# bop_pcb.net
KiCad netlist of a schematic drawn in EAGLE
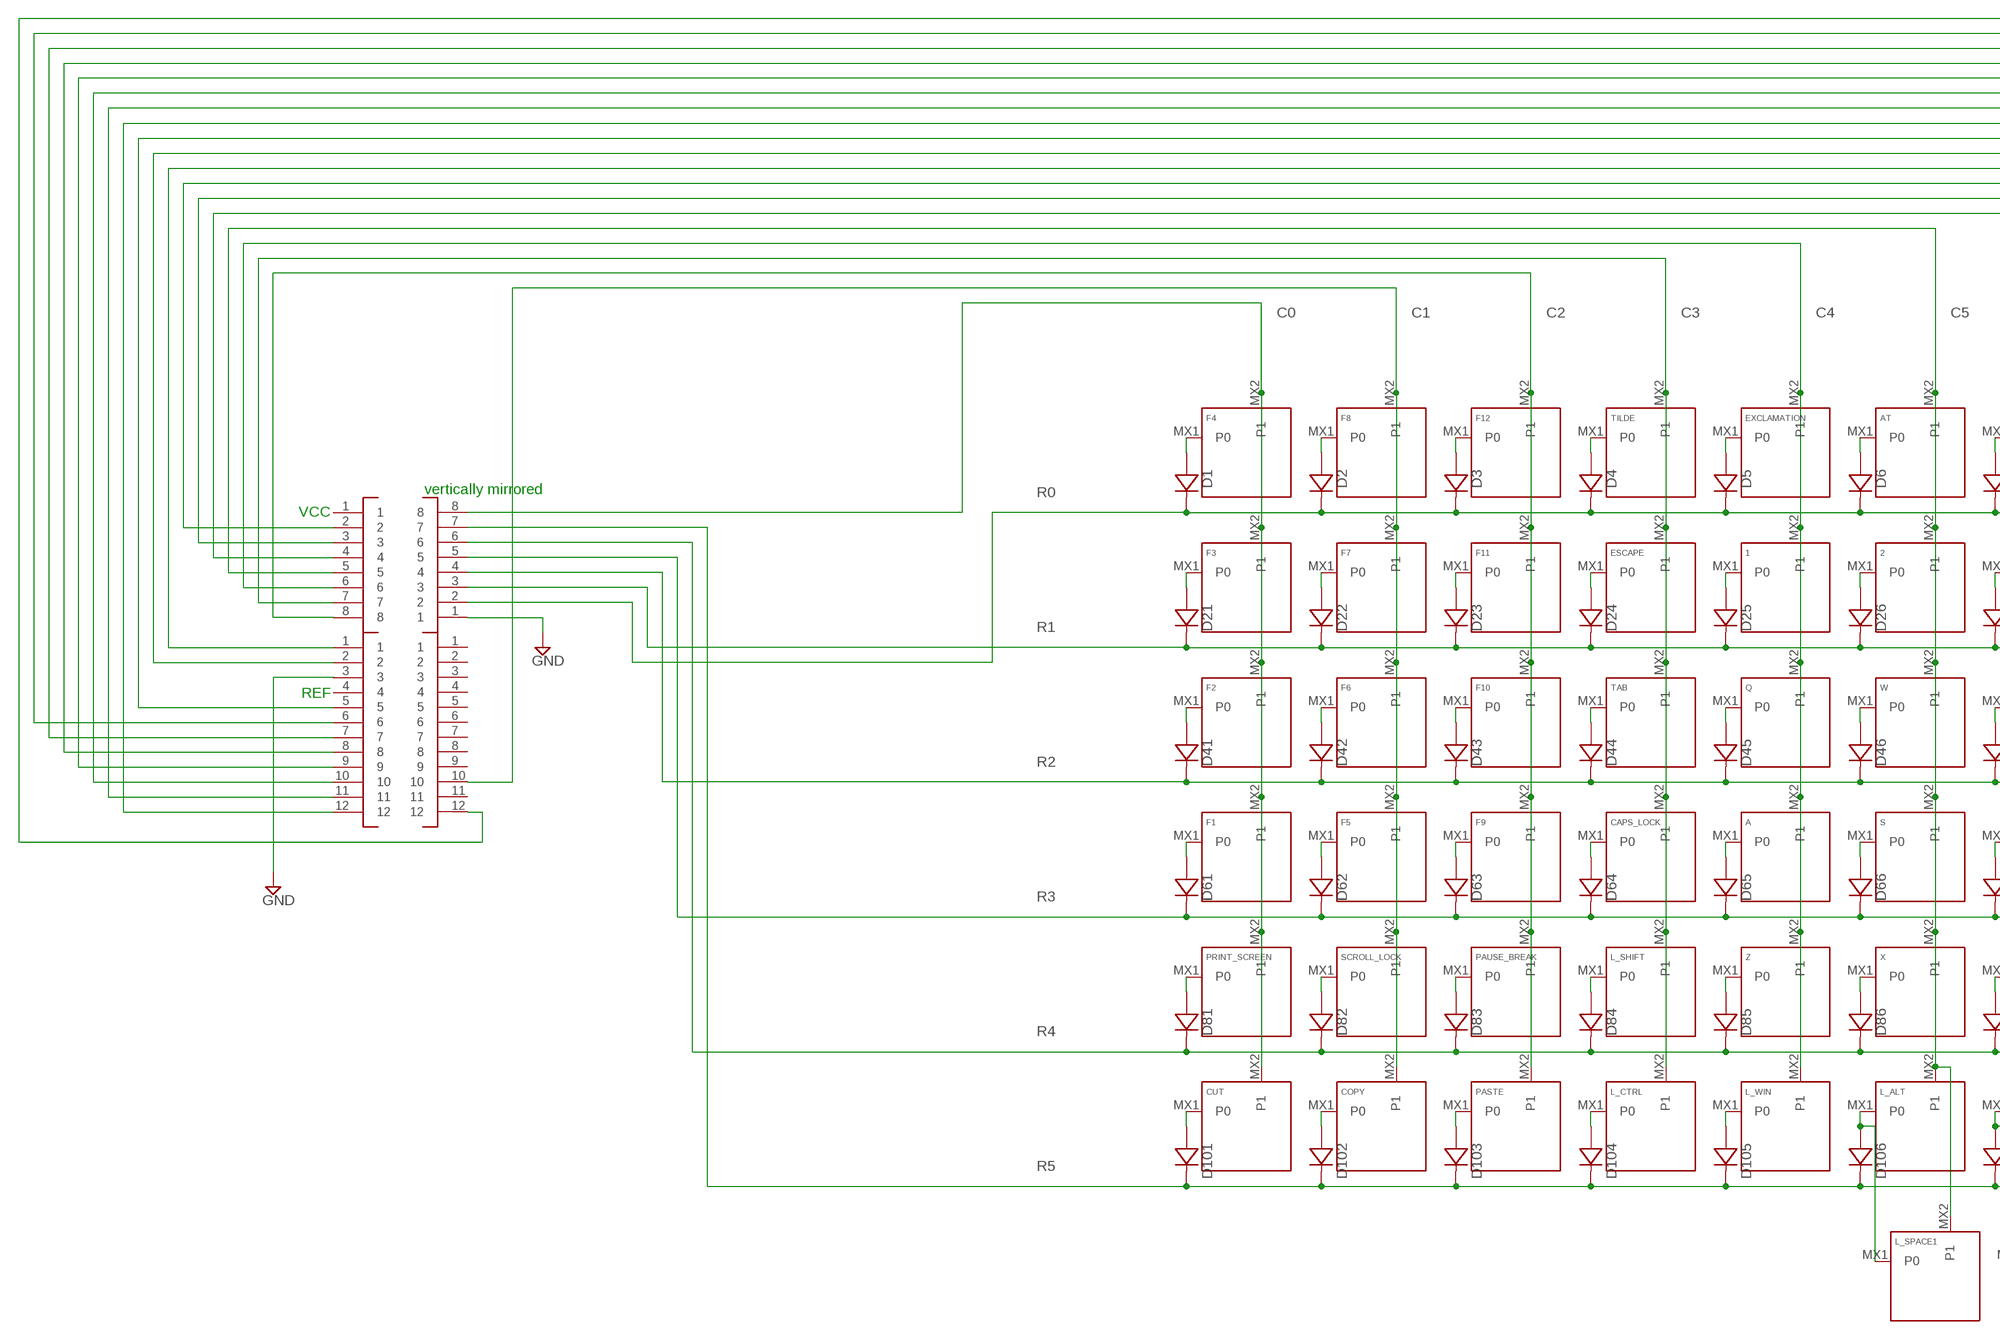
[diagram p0: schematic, sheet 1, part 1 of 2]
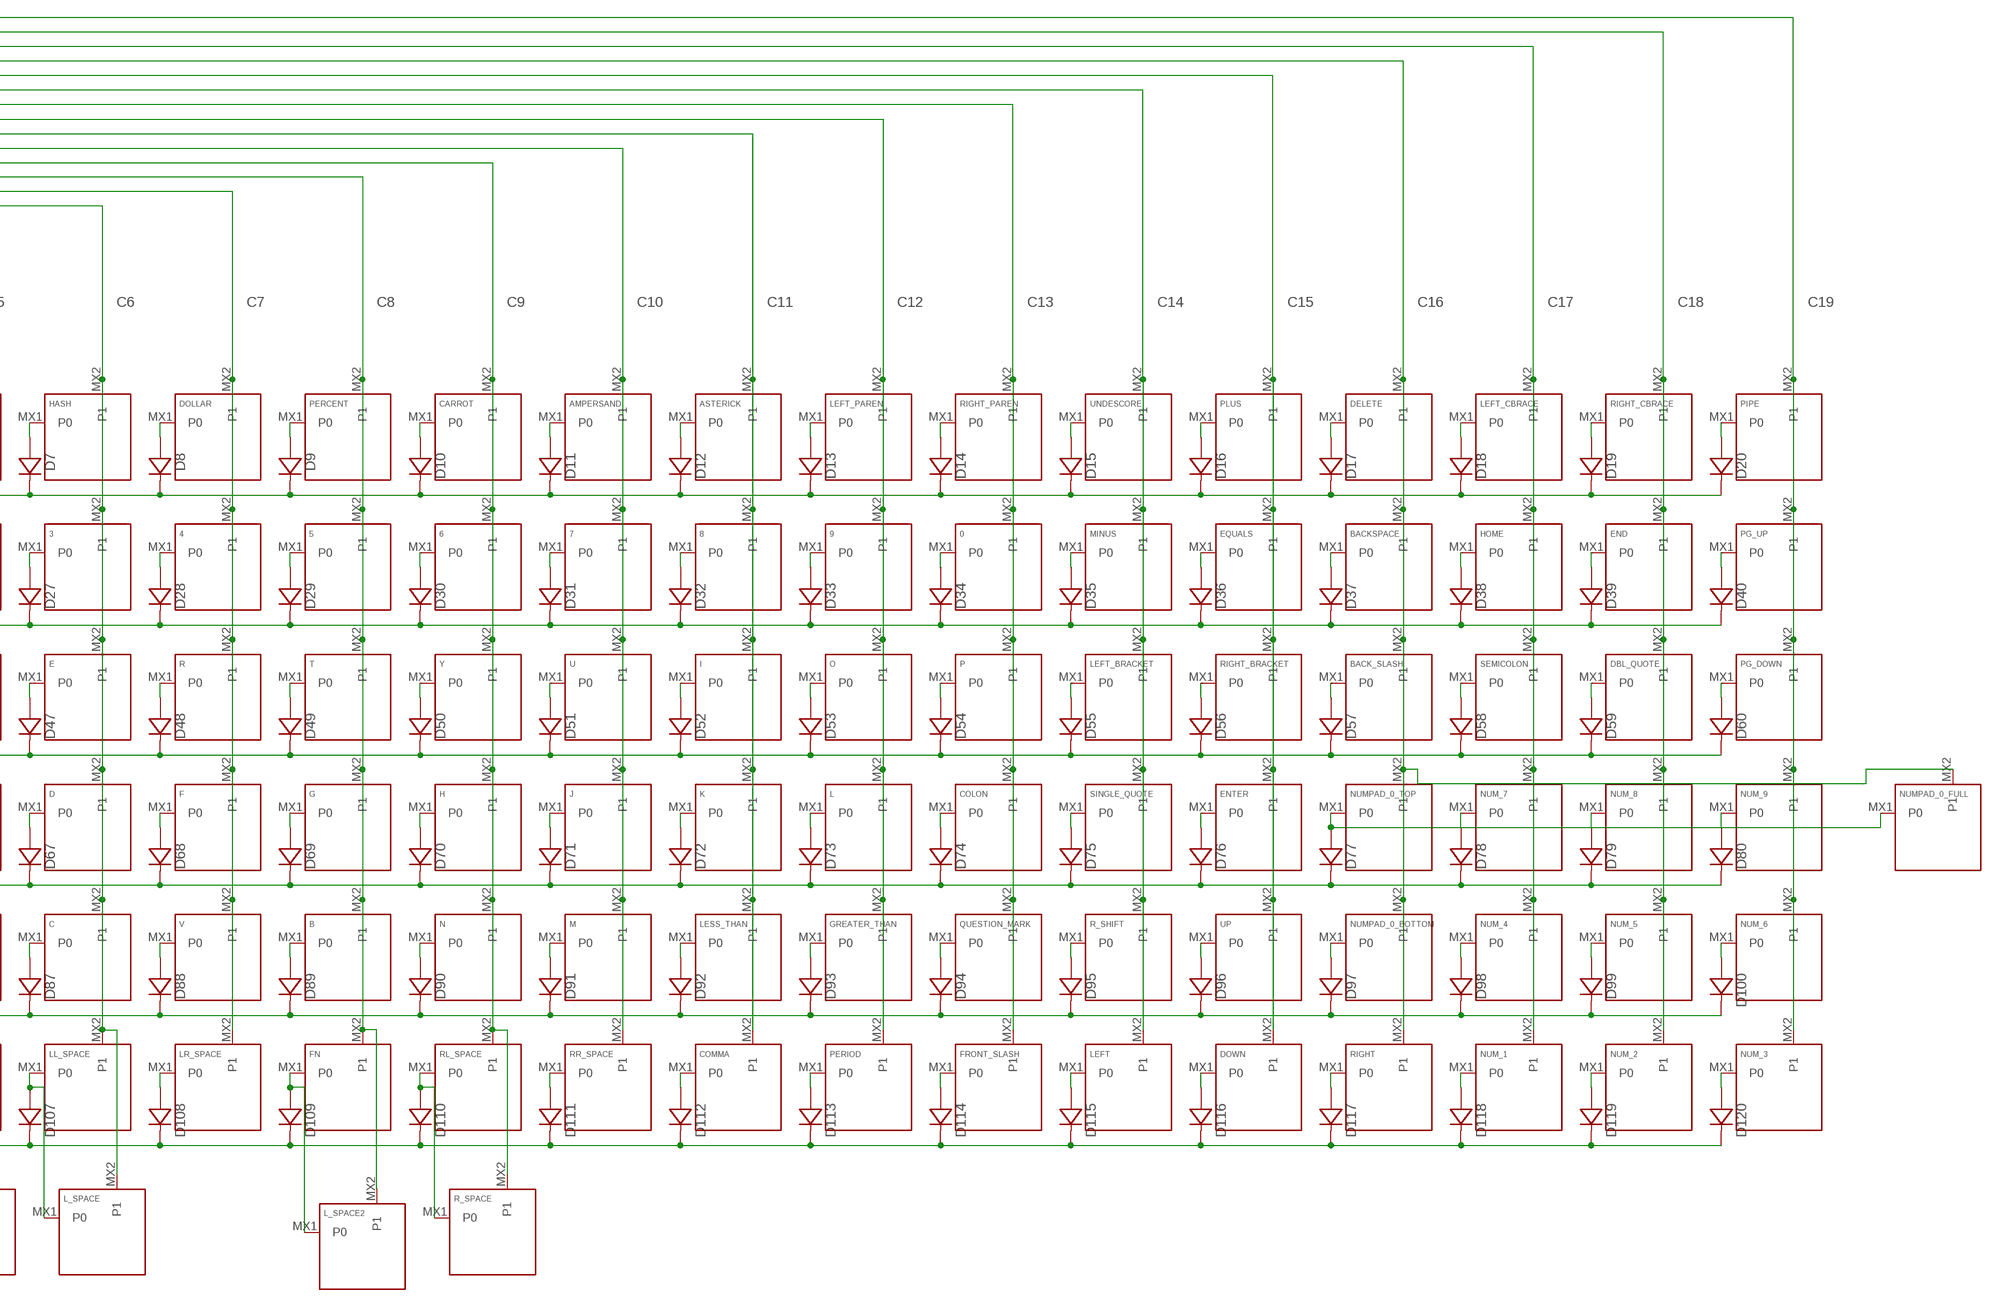
[diagram p1: schematic, sheet 1, part 2 of 2]

(export (version "E")
  (design (tool "Eeschema 10.0.6"))
  (components
    (comp (ref "0")
      (value "KEYSWITCH-PLAIN-MX-1U")
      (footprint "eagle-import:MX-1U")
      (libsource (lib "eagle-import") (part "KEYSWITCH-PLAIN-MX-1U"))
    )
    (comp (ref "1")
      (value "KEYSWITCH-PLAIN-MX-1U")
      (footprint "eagle-import:MX-1U")
      (libsource (lib "eagle-import") (part "KEYSWITCH-PLAIN-MX-1U"))
    )
    (comp (ref "2")
      (value "KEYSWITCH-PLAIN-MX-1U")
      (footprint "eagle-import:MX-1U")
      (libsource (lib "eagle-import") (part "KEYSWITCH-PLAIN-MX-1U"))
    )
    (comp (ref "3")
      (value "KEYSWITCH-PLAIN-MX-1U")
      (footprint "eagle-import:MX-1U")
      (libsource (lib "eagle-import") (part "KEYSWITCH-PLAIN-MX-1U"))
    )
    (comp (ref "4")
      (value "KEYSWITCH-PLAIN-MX-1U")
      (footprint "eagle-import:MX-1U")
      (libsource (lib "eagle-import") (part "KEYSWITCH-PLAIN-MX-1U"))
    )
    (comp (ref "5")
      (value "KEYSWITCH-PLAIN-MX-1U")
      (footprint "eagle-import:MX-1U")
      (libsource (lib "eagle-import") (part "KEYSWITCH-PLAIN-MX-1U"))
    )
    (comp (ref "6")
      (value "KEYSWITCH-PLAIN-MX-1U")
      (footprint "eagle-import:MX-1U")
      (libsource (lib "eagle-import") (part "KEYSWITCH-PLAIN-MX-1U"))
    )
    (comp (ref "7")
      (value "KEYSWITCH-PLAIN-MX-1U")
      (footprint "eagle-import:MX-1U")
      (libsource (lib "eagle-import") (part "KEYSWITCH-PLAIN-MX-1U"))
    )
    (comp (ref "8")
      (value "KEYSWITCH-PLAIN-MX-1U")
      (footprint "eagle-import:MX-1U")
      (libsource (lib "eagle-import") (part "KEYSWITCH-PLAIN-MX-1U"))
    )
    (comp (ref "9")
      (value "KEYSWITCH-PLAIN-MX-1U")
      (footprint "eagle-import:MX-1U")
      (libsource (lib "eagle-import") (part "KEYSWITCH-PLAIN-MX-1U"))
    )
    (comp (ref "A")
      (value "KEYSWITCH-PLAIN-MX-1U")
      (footprint "eagle-import:MX-1U")
      (libsource (lib "eagle-import") (part "KEYSWITCH-PLAIN-MX-1U"))
    )
    (comp (ref "AMPERSAND")
      (value "KEYSWITCH-PLAIN-MX-1U")
      (footprint "eagle-import:MX-1U")
      (libsource (lib "eagle-import") (part "KEYSWITCH-PLAIN-MX-1U"))
    )
    (comp (ref "ASTERICK")
      (value "KEYSWITCH-PLAIN-MX-1U")
      (footprint "eagle-import:MX-1U")
      (libsource (lib "eagle-import") (part "KEYSWITCH-PLAIN-MX-1U"))
    )
    (comp (ref "AT")
      (value "KEYSWITCH-PLAIN-MX-1U")
      (footprint "eagle-import:MX-1U")
      (libsource (lib "eagle-import") (part "KEYSWITCH-PLAIN-MX-1U"))
    )
    (comp (ref "B")
      (value "KEYSWITCH-PLAIN-MX-1U")
      (footprint "eagle-import:MX-1U")
      (libsource (lib "eagle-import") (part "KEYSWITCH-PLAIN-MX-1U"))
    )
    (comp (ref "BACKSPACE")
      (value "KEYSWITCH-PLAIN-MX-1U")
      (footprint "eagle-import:MX-1U")
      (libsource (lib "eagle-import") (part "KEYSWITCH-PLAIN-MX-1U"))
    )
    (comp (ref "BACK_SLASH")
      (value "KEYSWITCH-PLAIN-MX-1U")
      (footprint "eagle-import:MX-1U")
      (libsource (lib "eagle-import") (part "KEYSWITCH-PLAIN-MX-1U"))
    )
    (comp (ref "C")
      (value "KEYSWITCH-PLAIN-MX-1U")
      (footprint "eagle-import:MX-1U")
      (libsource (lib "eagle-import") (part "KEYSWITCH-PLAIN-MX-1U"))
    )
    (comp (ref "CAPS_LOCK")
      (value "KEYSWITCH-PLAIN-MX-1U")
      (footprint "eagle-import:MX-1U")
      (libsource (lib "eagle-import") (part "KEYSWITCH-PLAIN-MX-1U"))
    )
    (comp (ref "CARROT")
      (value "KEYSWITCH-PLAIN-MX-1U")
      (footprint "eagle-import:MX-1U")
      (libsource (lib "eagle-import") (part "KEYSWITCH-PLAIN-MX-1U"))
    )
    (comp (ref "COLON")
      (value "KEYSWITCH-PLAIN-MX-1U")
      (footprint "eagle-import:MX-1U")
      (libsource (lib "eagle-import") (part "KEYSWITCH-PLAIN-MX-1U"))
    )
    (comp (ref "COMMA")
      (value "KEYSWITCH-PLAIN-MX-1U")
      (footprint "eagle-import:MX-1U")
      (libsource (lib "eagle-import") (part "KEYSWITCH-PLAIN-MX-1U"))
    )
    (comp (ref "COPY")
      (value "KEYSWITCH-PLAIN-MX-1U")
      (footprint "eagle-import:MX-1U")
      (libsource (lib "eagle-import") (part "KEYSWITCH-PLAIN-MX-1U"))
    )
    (comp (ref "CUT")
      (value "KEYSWITCH-PLAIN-MX-1U")
      (footprint "eagle-import:MX-1U")
      (libsource (lib "eagle-import") (part "KEYSWITCH-PLAIN-MX-1U"))
    )
    (comp (ref "D")
      (value "KEYSWITCH-PLAIN-MX-1U")
      (footprint "eagle-import:MX-1U")
      (libsource (lib "eagle-import") (part "KEYSWITCH-PLAIN-MX-1U"))
    )
    (comp (ref "D1")
      (value "DIODE-SOD-123")
      (footprint "eagle-import:SOD-123")
      (libsource (lib "eagle-import") (part "DIODE-SOD-123"))
    )
    (comp (ref "D2")
      (value "DIODE-SOD-123")
      (footprint "eagle-import:SOD-123")
      (libsource (lib "eagle-import") (part "DIODE-SOD-123"))
    )
    (comp (ref "D3")
      (value "DIODE-SOD-123")
      (footprint "eagle-import:SOD-123")
      (libsource (lib "eagle-import") (part "DIODE-SOD-123"))
    )
    (comp (ref "D4")
      (value "DIODE-SOD-123")
      (footprint "eagle-import:SOD-123")
      (libsource (lib "eagle-import") (part "DIODE-SOD-123"))
    )
    (comp (ref "D5")
      (value "DIODE-SOD-123")
      (footprint "eagle-import:SOD-123")
      (libsource (lib "eagle-import") (part "DIODE-SOD-123"))
    )
    (comp (ref "D6")
      (value "DIODE-SOD-123")
      (footprint "eagle-import:SOD-123")
      (libsource (lib "eagle-import") (part "DIODE-SOD-123"))
    )
    (comp (ref "D7")
      (value "DIODE-SOD-123")
      (footprint "eagle-import:SOD-123")
      (libsource (lib "eagle-import") (part "DIODE-SOD-123"))
    )
    (comp (ref "D8")
      (value "DIODE-SOD-123")
      (footprint "eagle-import:SOD-123")
      (libsource (lib "eagle-import") (part "DIODE-SOD-123"))
    )
    (comp (ref "D9")
      (value "DIODE-SOD-123")
      (footprint "eagle-import:SOD-123")
      (libsource (lib "eagle-import") (part "DIODE-SOD-123"))
    )
    (comp (ref "D10")
      (value "DIODE-SOD-123")
      (footprint "eagle-import:SOD-123")
      (libsource (lib "eagle-import") (part "DIODE-SOD-123"))
    )
    (comp (ref "D11")
      (value "DIODE-SOD-123")
      (footprint "eagle-import:SOD-123")
      (libsource (lib "eagle-import") (part "DIODE-SOD-123"))
    )
    (comp (ref "D12")
      (value "DIODE-SOD-123")
      (footprint "eagle-import:SOD-123")
      (libsource (lib "eagle-import") (part "DIODE-SOD-123"))
    )
    (comp (ref "D13")
      (value "DIODE-SOD-123")
      (footprint "eagle-import:SOD-123")
      (libsource (lib "eagle-import") (part "DIODE-SOD-123"))
    )
    (comp (ref "D14")
      (value "DIODE-SOD-123")
      (footprint "eagle-import:SOD-123")
      (libsource (lib "eagle-import") (part "DIODE-SOD-123"))
    )
    (comp (ref "D15")
      (value "DIODE-SOD-123")
      (footprint "eagle-import:SOD-123")
      (libsource (lib "eagle-import") (part "DIODE-SOD-123"))
    )
    (comp (ref "D16")
      (value "DIODE-SOD-123")
      (footprint "eagle-import:SOD-123")
      (libsource (lib "eagle-import") (part "DIODE-SOD-123"))
    )
    (comp (ref "D17")
      (value "DIODE-SOD-123")
      (footprint "eagle-import:SOD-123")
      (libsource (lib "eagle-import") (part "DIODE-SOD-123"))
    )
    (comp (ref "D18")
      (value "DIODE-SOD-123")
      (footprint "eagle-import:SOD-123")
      (libsource (lib "eagle-import") (part "DIODE-SOD-123"))
    )
    (comp (ref "D19")
      (value "DIODE-SOD-123")
      (footprint "eagle-import:SOD-123")
      (libsource (lib "eagle-import") (part "DIODE-SOD-123"))
    )
    (comp (ref "D20")
      (value "DIODE-SOD-123")
      (footprint "eagle-import:SOD-123")
      (libsource (lib "eagle-import") (part "DIODE-SOD-123"))
    )
    (comp (ref "D21")
      (value "DIODE-SOD-123")
      (footprint "eagle-import:SOD-123")
      (libsource (lib "eagle-import") (part "DIODE-SOD-123"))
    )
    (comp (ref "D22")
      (value "DIODE-SOD-123")
      (footprint "eagle-import:SOD-123")
      (libsource (lib "eagle-import") (part "DIODE-SOD-123"))
    )
    (comp (ref "D23")
      (value "DIODE-SOD-123")
      (footprint "eagle-import:SOD-123")
      (libsource (lib "eagle-import") (part "DIODE-SOD-123"))
    )
    (comp (ref "D24")
      (value "DIODE-SOD-123")
      (footprint "eagle-import:SOD-123")
      (libsource (lib "eagle-import") (part "DIODE-SOD-123"))
    )
    (comp (ref "D25")
      (value "DIODE-SOD-123")
      (footprint "eagle-import:SOD-123")
      (libsource (lib "eagle-import") (part "DIODE-SOD-123"))
    )
    (comp (ref "D26")
      (value "DIODE-SOD-123")
      (footprint "eagle-import:SOD-123")
      (libsource (lib "eagle-import") (part "DIODE-SOD-123"))
    )
    (comp (ref "D27")
      (value "DIODE-SOD-123")
      (footprint "eagle-import:SOD-123")
      (libsource (lib "eagle-import") (part "DIODE-SOD-123"))
    )
    (comp (ref "D28")
      (value "DIODE-SOD-123")
      (footprint "eagle-import:SOD-123")
      (libsource (lib "eagle-import") (part "DIODE-SOD-123"))
    )
    (comp (ref "D29")
      (value "DIODE-SOD-123")
      (footprint "eagle-import:SOD-123")
      (libsource (lib "eagle-import") (part "DIODE-SOD-123"))
    )
    (comp (ref "D30")
      (value "DIODE-SOD-123")
      (footprint "eagle-import:SOD-123")
      (libsource (lib "eagle-import") (part "DIODE-SOD-123"))
    )
    (comp (ref "D31")
      (value "DIODE-SOD-123")
      (footprint "eagle-import:SOD-123")
      (libsource (lib "eagle-import") (part "DIODE-SOD-123"))
    )
    (comp (ref "D32")
      (value "DIODE-SOD-123")
      (footprint "eagle-import:SOD-123")
      (libsource (lib "eagle-import") (part "DIODE-SOD-123"))
    )
    (comp (ref "D33")
      (value "DIODE-SOD-123")
      (footprint "eagle-import:SOD-123")
      (libsource (lib "eagle-import") (part "DIODE-SOD-123"))
    )
    (comp (ref "D34")
      (value "DIODE-SOD-123")
      (footprint "eagle-import:SOD-123")
      (libsource (lib "eagle-import") (part "DIODE-SOD-123"))
    )
    (comp (ref "D35")
      (value "DIODE-SOD-123")
      (footprint "eagle-import:SOD-123")
      (libsource (lib "eagle-import") (part "DIODE-SOD-123"))
    )
    (comp (ref "D36")
      (value "DIODE-SOD-123")
      (footprint "eagle-import:SOD-123")
      (libsource (lib "eagle-import") (part "DIODE-SOD-123"))
    )
    (comp (ref "D37")
      (value "DIODE-SOD-123")
      (footprint "eagle-import:SOD-123")
      (libsource (lib "eagle-import") (part "DIODE-SOD-123"))
    )
    (comp (ref "D38")
      (value "DIODE-SOD-123")
      (footprint "eagle-import:SOD-123")
      (libsource (lib "eagle-import") (part "DIODE-SOD-123"))
    )
    (comp (ref "D39")
      (value "DIODE-SOD-123")
      (footprint "eagle-import:SOD-123")
      (libsource (lib "eagle-import") (part "DIODE-SOD-123"))
    )
    (comp (ref "D40")
      (value "DIODE-SOD-123")
      (footprint "eagle-import:SOD-123")
      (libsource (lib "eagle-import") (part "DIODE-SOD-123"))
    )
    (comp (ref "D41")
      (value "DIODE-SOD-123")
      (footprint "eagle-import:SOD-123")
      (libsource (lib "eagle-import") (part "DIODE-SOD-123"))
    )
    (comp (ref "D42")
      (value "DIODE-SOD-123")
      (footprint "eagle-import:SOD-123")
      (libsource (lib "eagle-import") (part "DIODE-SOD-123"))
    )
    (comp (ref "D43")
      (value "DIODE-SOD-123")
      (footprint "eagle-import:SOD-123")
      (libsource (lib "eagle-import") (part "DIODE-SOD-123"))
    )
    (comp (ref "D44")
      (value "DIODE-SOD-123")
      (footprint "eagle-import:SOD-123")
      (libsource (lib "eagle-import") (part "DIODE-SOD-123"))
    )
    (comp (ref "D45")
      (value "DIODE-SOD-123")
      (footprint "eagle-import:SOD-123")
      (libsource (lib "eagle-import") (part "DIODE-SOD-123"))
    )
    (comp (ref "D46")
      (value "DIODE-SOD-123")
      (footprint "eagle-import:SOD-123")
      (libsource (lib "eagle-import") (part "DIODE-SOD-123"))
    )
    (comp (ref "D47")
      (value "DIODE-SOD-123")
      (footprint "eagle-import:SOD-123")
      (libsource (lib "eagle-import") (part "DIODE-SOD-123"))
    )
    (comp (ref "D48")
      (value "DIODE-SOD-123")
      (footprint "eagle-import:SOD-123")
      (libsource (lib "eagle-import") (part "DIODE-SOD-123"))
    )
    (comp (ref "D49")
      (value "DIODE-SOD-123")
      (footprint "eagle-import:SOD-123")
      (libsource (lib "eagle-import") (part "DIODE-SOD-123"))
    )
    (comp (ref "D50")
      (value "DIODE-SOD-123")
      (footprint "eagle-import:SOD-123")
      (libsource (lib "eagle-import") (part "DIODE-SOD-123"))
    )
    (comp (ref "D51")
      (value "DIODE-SOD-123")
      (footprint "eagle-import:SOD-123")
      (libsource (lib "eagle-import") (part "DIODE-SOD-123"))
    )
    (comp (ref "D52")
      (value "DIODE-SOD-123")
      (footprint "eagle-import:SOD-123")
      (libsource (lib "eagle-import") (part "DIODE-SOD-123"))
    )
    (comp (ref "D53")
      (value "DIODE-SOD-123")
      (footprint "eagle-import:SOD-123")
      (libsource (lib "eagle-import") (part "DIODE-SOD-123"))
    )
    (comp (ref "D54")
      (value "DIODE-SOD-123")
      (footprint "eagle-import:SOD-123")
      (libsource (lib "eagle-import") (part "DIODE-SOD-123"))
    )
    (comp (ref "D55")
      (value "DIODE-SOD-123")
      (footprint "eagle-import:SOD-123")
      (libsource (lib "eagle-import") (part "DIODE-SOD-123"))
    )
    (comp (ref "D56")
      (value "DIODE-SOD-123")
      (footprint "eagle-import:SOD-123")
      (libsource (lib "eagle-import") (part "DIODE-SOD-123"))
    )
    (comp (ref "D57")
      (value "DIODE-SOD-123")
      (footprint "eagle-import:SOD-123")
      (libsource (lib "eagle-import") (part "DIODE-SOD-123"))
    )
    (comp (ref "D58")
      (value "DIODE-SOD-123")
      (footprint "eagle-import:SOD-123")
      (libsource (lib "eagle-import") (part "DIODE-SOD-123"))
    )
    (comp (ref "D59")
      (value "DIODE-SOD-123")
      (footprint "eagle-import:SOD-123")
      (libsource (lib "eagle-import") (part "DIODE-SOD-123"))
    )
    (comp (ref "D60")
      (value "DIODE-SOD-123")
      (footprint "eagle-import:SOD-123")
      (libsource (lib "eagle-import") (part "DIODE-SOD-123"))
    )
    (comp (ref "D61")
      (value "DIODE-SOD-123")
      (footprint "eagle-import:SOD-123")
      (libsource (lib "eagle-import") (part "DIODE-SOD-123"))
    )
    (comp (ref "D62")
      (value "DIODE-SOD-123")
      (footprint "eagle-import:SOD-123")
      (libsource (lib "eagle-import") (part "DIODE-SOD-123"))
    )
    (comp (ref "D63")
      (value "DIODE-SOD-123")
      (footprint "eagle-import:SOD-123")
      (libsource (lib "eagle-import") (part "DIODE-SOD-123"))
    )
    (comp (ref "D64")
      (value "DIODE-SOD-123")
      (footprint "eagle-import:SOD-123")
      (libsource (lib "eagle-import") (part "DIODE-SOD-123"))
    )
    (comp (ref "D65")
      (value "DIODE-SOD-123")
      (footprint "eagle-import:SOD-123")
      (libsource (lib "eagle-import") (part "DIODE-SOD-123"))
    )
    (comp (ref "D66")
      (value "DIODE-SOD-123")
      (footprint "eagle-import:SOD-123")
      (libsource (lib "eagle-import") (part "DIODE-SOD-123"))
    )
    (comp (ref "D67")
      (value "DIODE-SOD-123")
      (footprint "eagle-import:SOD-123")
      (libsource (lib "eagle-import") (part "DIODE-SOD-123"))
    )
    (comp (ref "D68")
      (value "DIODE-SOD-123")
      (footprint "eagle-import:SOD-123")
      (libsource (lib "eagle-import") (part "DIODE-SOD-123"))
    )
    (comp (ref "D69")
      (value "DIODE-SOD-123")
      (footprint "eagle-import:SOD-123")
      (libsource (lib "eagle-import") (part "DIODE-SOD-123"))
    )
    (comp (ref "D70")
      (value "DIODE-SOD-123")
      (footprint "eagle-import:SOD-123")
      (libsource (lib "eagle-import") (part "DIODE-SOD-123"))
    )
    (comp (ref "D71")
      (value "DIODE-SOD-123")
      (footprint "eagle-import:SOD-123")
      (libsource (lib "eagle-import") (part "DIODE-SOD-123"))
    )
    (comp (ref "D72")
      (value "DIODE-SOD-123")
      (footprint "eagle-import:SOD-123")
      (libsource (lib "eagle-import") (part "DIODE-SOD-123"))
    )
    (comp (ref "D73")
      (value "DIODE-SOD-123")
      (footprint "eagle-import:SOD-123")
      (libsource (lib "eagle-import") (part "DIODE-SOD-123"))
    )
    (comp (ref "D74")
      (value "DIODE-SOD-123")
      (footprint "eagle-import:SOD-123")
      (libsource (lib "eagle-import") (part "DIODE-SOD-123"))
    )
    (comp (ref "D75")
      (value "DIODE-SOD-123")
      (footprint "eagle-import:SOD-123")
      (libsource (lib "eagle-import") (part "DIODE-SOD-123"))
    )
    (comp (ref "D76")
      (value "DIODE-SOD-123")
      (footprint "eagle-import:SOD-123")
      (libsource (lib "eagle-import") (part "DIODE-SOD-123"))
    )
    (comp (ref "D77")
      (value "DIODE-SOD-123")
      (footprint "eagle-import:SOD-123")
      (libsource (lib "eagle-import") (part "DIODE-SOD-123"))
    )
    (comp (ref "D78")
      (value "DIODE-SOD-123")
      (footprint "eagle-import:SOD-123")
      (libsource (lib "eagle-import") (part "DIODE-SOD-123"))
    )
    (comp (ref "D79")
      (value "DIODE-SOD-123")
      (footprint "eagle-import:SOD-123")
      (libsource (lib "eagle-import") (part "DIODE-SOD-123"))
    )
    (comp (ref "D80")
      (value "DIODE-SOD-123")
      (footprint "eagle-import:SOD-123")
      (libsource (lib "eagle-import") (part "DIODE-SOD-123"))
    )
    (comp (ref "D81")
      (value "DIODE-SOD-123")
      (footprint "eagle-import:SOD-123")
      (libsource (lib "eagle-import") (part "DIODE-SOD-123"))
    )
    (comp (ref "D82")
      (value "DIODE-SOD-123")
      (footprint "eagle-import:SOD-123")
      (libsource (lib "eagle-import") (part "DIODE-SOD-123"))
    )
    (comp (ref "D83")
      (value "DIODE-SOD-123")
      (footprint "eagle-import:SOD-123")
      (libsource (lib "eagle-import") (part "DIODE-SOD-123"))
    )
    (comp (ref "D84")
      (value "DIODE-SOD-123")
      (footprint "eagle-import:SOD-123")
      (libsource (lib "eagle-import") (part "DIODE-SOD-123"))
    )
    (comp (ref "D85")
      (value "DIODE-SOD-123")
      (footprint "eagle-import:SOD-123")
      (libsource (lib "eagle-import") (part "DIODE-SOD-123"))
    )
    (comp (ref "D86")
      (value "DIODE-SOD-123")
      (footprint "eagle-import:SOD-123")
      (libsource (lib "eagle-import") (part "DIODE-SOD-123"))
    )
    (comp (ref "D87")
      (value "DIODE-SOD-123")
      (footprint "eagle-import:SOD-123")
      (libsource (lib "eagle-import") (part "DIODE-SOD-123"))
    )
    (comp (ref "D88")
      (value "DIODE-SOD-123")
      (footprint "eagle-import:SOD-123")
      (libsource (lib "eagle-import") (part "DIODE-SOD-123"))
    )
    (comp (ref "D89")
      (value "DIODE-SOD-123")
      (footprint "eagle-import:SOD-123")
      (libsource (lib "eagle-import") (part "DIODE-SOD-123"))
    )
    (comp (ref "D90")
      (value "DIODE-SOD-123")
      (footprint "eagle-import:SOD-123")
      (libsource (lib "eagle-import") (part "DIODE-SOD-123"))
    )
    (comp (ref "D91")
      (value "DIODE-SOD-123")
      (footprint "eagle-import:SOD-123")
      (libsource (lib "eagle-import") (part "DIODE-SOD-123"))
    )
    (comp (ref "D92")
      (value "DIODE-SOD-123")
      (footprint "eagle-import:SOD-123")
      (libsource (lib "eagle-import") (part "DIODE-SOD-123"))
    )
    (comp (ref "D93")
      (value "DIODE-SOD-123")
      (footprint "eagle-import:SOD-123")
      (libsource (lib "eagle-import") (part "DIODE-SOD-123"))
    )
    (comp (ref "D94")
      (value "DIODE-SOD-123")
      (footprint "eagle-import:SOD-123")
      (libsource (lib "eagle-import") (part "DIODE-SOD-123"))
    )
    (comp (ref "D95")
      (value "DIODE-SOD-123")
      (footprint "eagle-import:SOD-123")
      (libsource (lib "eagle-import") (part "DIODE-SOD-123"))
    )
    (comp (ref "D96")
      (value "DIODE-SOD-123")
      (footprint "eagle-import:SOD-123")
      (libsource (lib "eagle-import") (part "DIODE-SOD-123"))
    )
    (comp (ref "D97")
      (value "DIODE-SOD-123")
      (footprint "eagle-import:SOD-123")
      (libsource (lib "eagle-import") (part "DIODE-SOD-123"))
    )
    (comp (ref "D98")
      (value "DIODE-SOD-123")
      (footprint "eagle-import:SOD-123")
      (libsource (lib "eagle-import") (part "DIODE-SOD-123"))
    )
    (comp (ref "D99")
      (value "DIODE-SOD-123")
      (footprint "eagle-import:SOD-123")
      (libsource (lib "eagle-import") (part "DIODE-SOD-123"))
    )
    (comp (ref "D100")
      (value "DIODE-SOD-123")
      (footprint "eagle-import:SOD-123")
      (libsource (lib "eagle-import") (part "DIODE-SOD-123"))
    )
    (comp (ref "D101")
      (value "DIODE-SOD-123")
      (footprint "eagle-import:SOD-123")
      (libsource (lib "eagle-import") (part "DIODE-SOD-123"))
    )
    (comp (ref "D102")
      (value "DIODE-SOD-123")
      (footprint "eagle-import:SOD-123")
      (libsource (lib "eagle-import") (part "DIODE-SOD-123"))
    )
    (comp (ref "D103")
      (value "DIODE-SOD-123")
      (footprint "eagle-import:SOD-123")
      (libsource (lib "eagle-import") (part "DIODE-SOD-123"))
    )
    (comp (ref "D104")
      (value "DIODE-SOD-123")
      (footprint "eagle-import:SOD-123")
      (libsource (lib "eagle-import") (part "DIODE-SOD-123"))
    )
    (comp (ref "D105")
      (value "DIODE-SOD-123")
      (footprint "eagle-import:SOD-123")
      (libsource (lib "eagle-import") (part "DIODE-SOD-123"))
    )
    (comp (ref "D106")
      (value "DIODE-SOD-123")
      (footprint "eagle-import:SOD-123")
      (libsource (lib "eagle-import") (part "DIODE-SOD-123"))
    )
    (comp (ref "D107")
      (value "DIODE-SOD-123")
      (footprint "eagle-import:SOD-123")
      (libsource (lib "eagle-import") (part "DIODE-SOD-123"))
    )
    (comp (ref "D108")
      (value "DIODE-SOD-123")
      (footprint "eagle-import:SOD-123")
      (libsource (lib "eagle-import") (part "DIODE-SOD-123"))
    )
    (comp (ref "D109")
      (value "DIODE-SOD-123")
      (footprint "eagle-import:SOD-123")
      (libsource (lib "eagle-import") (part "DIODE-SOD-123"))
    )
    (comp (ref "D110")
      (value "DIODE-SOD-123")
      (footprint "eagle-import:SOD-123")
      (libsource (lib "eagle-import") (part "DIODE-SOD-123"))
    )
    (comp (ref "D111")
      (value "DIODE-SOD-123")
      (footprint "eagle-import:SOD-123")
      (libsource (lib "eagle-import") (part "DIODE-SOD-123"))
    )
    (comp (ref "D112")
      (value "DIODE-SOD-123")
      (footprint "eagle-import:SOD-123")
      (libsource (lib "eagle-import") (part "DIODE-SOD-123"))
    )
    (comp (ref "D113")
      (value "DIODE-SOD-123")
      (footprint "eagle-import:SOD-123")
      (libsource (lib "eagle-import") (part "DIODE-SOD-123"))
    )
    (comp (ref "D114")
      (value "DIODE-SOD-123")
      (footprint "eagle-import:SOD-123")
      (libsource (lib "eagle-import") (part "DIODE-SOD-123"))
    )
    (comp (ref "D115")
      (value "DIODE-SOD-123")
      (footprint "eagle-import:SOD-123")
      (libsource (lib "eagle-import") (part "DIODE-SOD-123"))
    )
    (comp (ref "D116")
      (value "DIODE-SOD-123")
      (footprint "eagle-import:SOD-123")
      (libsource (lib "eagle-import") (part "DIODE-SOD-123"))
    )
    (comp (ref "D117")
      (value "DIODE-SOD-123")
      (footprint "eagle-import:SOD-123")
      (libsource (lib "eagle-import") (part "DIODE-SOD-123"))
    )
    (comp (ref "D118")
      (value "DIODE-SOD-123")
      (footprint "eagle-import:SOD-123")
      (libsource (lib "eagle-import") (part "DIODE-SOD-123"))
    )
    (comp (ref "D119")
      (value "DIODE-SOD-123")
      (footprint "eagle-import:SOD-123")
      (libsource (lib "eagle-import") (part "DIODE-SOD-123"))
    )
    (comp (ref "D120")
      (value "DIODE-SOD-123")
      (footprint "eagle-import:SOD-123")
      (libsource (lib "eagle-import") (part "DIODE-SOD-123"))
    )
    (comp (ref "DBL_QUOTE")
      (value "KEYSWITCH-PLAIN-MX-1U")
      (footprint "eagle-import:MX-1U")
      (libsource (lib "eagle-import") (part "KEYSWITCH-PLAIN-MX-1U"))
    )
    (comp (ref "DELETE")
      (value "KEYSWITCH-PLAIN-MX-1U")
      (footprint "eagle-import:MX-1U")
      (libsource (lib "eagle-import") (part "KEYSWITCH-PLAIN-MX-1U"))
    )
    (comp (ref "DOLLAR")
      (value "KEYSWITCH-PLAIN-MX-1U")
      (footprint "eagle-import:MX-1U")
      (libsource (lib "eagle-import") (part "KEYSWITCH-PLAIN-MX-1U"))
    )
    (comp (ref "DOWN")
      (value "KEYSWITCH-PLAIN-MX-1U")
      (footprint "eagle-import:MX-1U")
      (libsource (lib "eagle-import") (part "KEYSWITCH-PLAIN-MX-1U"))
    )
    (comp (ref "E")
      (value "KEYSWITCH-PLAIN-MX-1U")
      (footprint "eagle-import:MX-1U")
      (libsource (lib "eagle-import") (part "KEYSWITCH-PLAIN-MX-1U"))
    )
    (comp (ref "END")
      (value "KEYSWITCH-PLAIN-MX-1U")
      (footprint "eagle-import:MX-1U")
      (libsource (lib "eagle-import") (part "KEYSWITCH-PLAIN-MX-1U"))
    )
    (comp (ref "ENTER")
      (value "KEYSWITCH-PLAIN-MX-1U")
      (footprint "eagle-import:MX-1U")
      (libsource (lib "eagle-import") (part "KEYSWITCH-PLAIN-MX-1U"))
    )
    (comp (ref "EQUALS")
      (value "KEYSWITCH-PLAIN-MX-1U")
      (footprint "eagle-import:MX-1U")
      (libsource (lib "eagle-import") (part "KEYSWITCH-PLAIN-MX-1U"))
    )
    (comp (ref "ESCAPE")
      (value "KEYSWITCH-PLAIN-MX-1U")
      (footprint "eagle-import:MX-1U")
      (libsource (lib "eagle-import") (part "KEYSWITCH-PLAIN-MX-1U"))
    )
    (comp (ref "EXCLAMATION")
      (value "KEYSWITCH-PLAIN-MX-1U")
      (footprint "eagle-import:MX-1U")
      (libsource (lib "eagle-import") (part "KEYSWITCH-PLAIN-MX-1U"))
    )
    (comp (ref "F")
      (value "KEYSWITCH-PLAIN-MX-1U")
      (footprint "eagle-import:MX-1U")
      (libsource (lib "eagle-import") (part "KEYSWITCH-PLAIN-MX-1U"))
    )
    (comp (ref "F1")
      (value "KEYSWITCH-PLAIN-MX-1U")
      (footprint "eagle-import:MX-1U")
      (libsource (lib "eagle-import") (part "KEYSWITCH-PLAIN-MX-1U"))
    )
    (comp (ref "F2")
      (value "KEYSWITCH-PLAIN-MX-1U")
      (footprint "eagle-import:MX-1U")
      (libsource (lib "eagle-import") (part "KEYSWITCH-PLAIN-MX-1U"))
    )
    (comp (ref "F3")
      (value "KEYSWITCH-PLAIN-MX-1U")
      (footprint "eagle-import:MX-1U")
      (libsource (lib "eagle-import") (part "KEYSWITCH-PLAIN-MX-1U"))
    )
    (comp (ref "F4")
      (value "KEYSWITCH-PLAIN-MX-1U")
      (footprint "eagle-import:MX-1U")
      (libsource (lib "eagle-import") (part "KEYSWITCH-PLAIN-MX-1U"))
    )
    (comp (ref "F5")
      (value "KEYSWITCH-PLAIN-MX-1U")
      (footprint "eagle-import:MX-1U")
      (libsource (lib "eagle-import") (part "KEYSWITCH-PLAIN-MX-1U"))
    )
    (comp (ref "F6")
      (value "KEYSWITCH-PLAIN-MX-1U")
      (footprint "eagle-import:MX-1U")
      (libsource (lib "eagle-import") (part "KEYSWITCH-PLAIN-MX-1U"))
    )
    (comp (ref "F7")
      (value "KEYSWITCH-PLAIN-MX-1U")
      (footprint "eagle-import:MX-1U")
      (libsource (lib "eagle-import") (part "KEYSWITCH-PLAIN-MX-1U"))
    )
    (comp (ref "F8")
      (value "KEYSWITCH-PLAIN-MX-1U")
      (footprint "eagle-import:MX-1U")
      (libsource (lib "eagle-import") (part "KEYSWITCH-PLAIN-MX-1U"))
    )
    (comp (ref "F9")
      (value "KEYSWITCH-PLAIN-MX-1U")
      (footprint "eagle-import:MX-1U")
      (libsource (lib "eagle-import") (part "KEYSWITCH-PLAIN-MX-1U"))
    )
    (comp (ref "F10")
      (value "KEYSWITCH-PLAIN-MX-1U")
      (footprint "eagle-import:MX-1U")
      (libsource (lib "eagle-import") (part "KEYSWITCH-PLAIN-MX-1U"))
    )
    (comp (ref "F11")
      (value "KEYSWITCH-PLAIN-MX-1U")
      (footprint "eagle-import:MX-1U")
      (libsource (lib "eagle-import") (part "KEYSWITCH-PLAIN-MX-1U"))
    )
    (comp (ref "F12")
      (value "KEYSWITCH-PLAIN-MX-1U")
      (footprint "eagle-import:MX-1U")
      (libsource (lib "eagle-import") (part "KEYSWITCH-PLAIN-MX-1U"))
    )
    (comp (ref "FN")
      (value "KEYSWITCH-PLAIN-MX-1U")
      (footprint "eagle-import:MX-1U")
      (libsource (lib "eagle-import") (part "KEYSWITCH-PLAIN-MX-1U"))
    )
    (comp (ref "FRONT_SLASH")
      (value "KEYSWITCH-PLAIN-MX-1U")
      (footprint "eagle-import:MX-1U")
      (libsource (lib "eagle-import") (part "KEYSWITCH-PLAIN-MX-1U"))
    )
    (comp (ref "G")
      (value "KEYSWITCH-PLAIN-MX-1U")
      (footprint "eagle-import:MX-1U")
      (libsource (lib "eagle-import") (part "KEYSWITCH-PLAIN-MX-1U"))
    )
    (comp (ref "GREATER_THAN")
      (value "KEYSWITCH-PLAIN-MX-1U")
      (footprint "eagle-import:MX-1U")
      (libsource (lib "eagle-import") (part "KEYSWITCH-PLAIN-MX-1U"))
    )
    (comp (ref "H")
      (value "KEYSWITCH-PLAIN-MX-1U")
      (footprint "eagle-import:MX-1U")
      (libsource (lib "eagle-import") (part "KEYSWITCH-PLAIN-MX-1U"))
    )
    (comp (ref "HASH")
      (value "KEYSWITCH-PLAIN-MX-1U")
      (footprint "eagle-import:MX-1U")
      (libsource (lib "eagle-import") (part "KEYSWITCH-PLAIN-MX-1U"))
    )
    (comp (ref "HOME")
      (value "KEYSWITCH-PLAIN-MX-1U")
      (footprint "eagle-import:MX-1U")
      (libsource (lib "eagle-import") (part "KEYSWITCH-PLAIN-MX-1U"))
    )
    (comp (ref "I")
      (value "KEYSWITCH-PLAIN-MX-1U")
      (footprint "eagle-import:MX-1U")
      (libsource (lib "eagle-import") (part "KEYSWITCH-PLAIN-MX-1U"))
    )
    (comp (ref "J")
      (value "KEYSWITCH-PLAIN-MX-1U")
      (footprint "eagle-import:MX-1U")
      (libsource (lib "eagle-import") (part "KEYSWITCH-PLAIN-MX-1U"))
    )
    (comp (ref "J1")
      (value "HEADER-12X1-2.54-ROUND")
      (footprint "eagle-import:HEADER-12X1-2.54-ROUND")
      (libsource (lib "eagle-import") (part "HEADER-12X1-2.54-ROUND"))
    )
    (comp (ref "J2")
      (value "HEADER-12X1-2.54-ROUND")
      (footprint "eagle-import:HEADER-12X1-2.54-ROUND")
      (libsource (lib "eagle-import") (part "HEADER-12X1-2.54-ROUND"))
    )
    (comp (ref "K")
      (value "KEYSWITCH-PLAIN-MX-1U")
      (footprint "eagle-import:MX-1U")
      (libsource (lib "eagle-import") (part "KEYSWITCH-PLAIN-MX-1U"))
    )
    (comp (ref "L")
      (value "KEYSWITCH-PLAIN-MX-1U")
      (footprint "eagle-import:MX-1U")
      (libsource (lib "eagle-import") (part "KEYSWITCH-PLAIN-MX-1U"))
    )
    (comp (ref "LEFT")
      (value "KEYSWITCH-PLAIN-MX-1U")
      (footprint "eagle-import:MX-1U")
      (libsource (lib "eagle-import") (part "KEYSWITCH-PLAIN-MX-1U"))
    )
    (comp (ref "LEFT_BRACKET")
      (value "KEYSWITCH-PLAIN-MX-1U")
      (footprint "eagle-import:MX-1U")
      (libsource (lib "eagle-import") (part "KEYSWITCH-PLAIN-MX-1U"))
    )
    (comp (ref "LEFT_CBRACE")
      (value "KEYSWITCH-PLAIN-MX-1U")
      (footprint "eagle-import:MX-1U")
      (libsource (lib "eagle-import") (part "KEYSWITCH-PLAIN-MX-1U"))
    )
    (comp (ref "LEFT_PAREN")
      (value "KEYSWITCH-PLAIN-MX-1U")
      (footprint "eagle-import:MX-1U")
      (libsource (lib "eagle-import") (part "KEYSWITCH-PLAIN-MX-1U"))
    )
    (comp (ref "LESS_THAN")
      (value "KEYSWITCH-PLAIN-MX-1U")
      (footprint "eagle-import:MX-1U")
      (libsource (lib "eagle-import") (part "KEYSWITCH-PLAIN-MX-1U"))
    )
    (comp (ref "LL_SPACE")
      (value "KEYSWITCH-PLAIN-MX-1U")
      (footprint "eagle-import:MX-1U")
      (libsource (lib "eagle-import") (part "KEYSWITCH-PLAIN-MX-1U"))
    )
    (comp (ref "LR_SPACE")
      (value "KEYSWITCH-PLAIN-MX-1U")
      (footprint "eagle-import:MX-1U")
      (libsource (lib "eagle-import") (part "KEYSWITCH-PLAIN-MX-1U"))
    )
    (comp (ref "L_ALT")
      (value "KEYSWITCH-PLAIN-MX-1U")
      (footprint "eagle-import:MX-1U")
      (libsource (lib "eagle-import") (part "KEYSWITCH-PLAIN-MX-1U"))
    )
    (comp (ref "L_CTRL")
      (value "KEYSWITCH-PLAIN-MX-1U")
      (footprint "eagle-import:MX-1U")
      (libsource (lib "eagle-import") (part "KEYSWITCH-PLAIN-MX-1U"))
    )
    (comp (ref "L_SHIFT")
      (value "KEYSWITCH-PLAIN-MX-1U")
      (footprint "eagle-import:MX-1U")
      (libsource (lib "eagle-import") (part "KEYSWITCH-PLAIN-MX-1U"))
    )
    (comp (ref "L_SPACE")
      (value "KEYSWITCH-PLAIN-MX-2U")
      (footprint "eagle-import:MX-2U")
      (libsource (lib "eagle-import") (part "KEYSWITCH-PLAIN-MX-2U"))
    )
    (comp (ref "L_SPACE1")
      (value "KEYSWITCH-PLAIN-MX-2U")
      (footprint "eagle-import:MX-2U")
      (libsource (lib "eagle-import") (part "KEYSWITCH-PLAIN-MX-2U"))
    )
    (comp (ref "L_SPACE2")
      (value "KEYSWITCH-PLAIN-MX-2U")
      (footprint "eagle-import:MX-2U")
      (libsource (lib "eagle-import") (part "KEYSWITCH-PLAIN-MX-2U"))
    )
    (comp (ref "L_WIN")
      (value "KEYSWITCH-PLAIN-MX-1U")
      (footprint "eagle-import:MX-1U")
      (libsource (lib "eagle-import") (part "KEYSWITCH-PLAIN-MX-1U"))
    )
    (comp (ref "M")
      (value "KEYSWITCH-PLAIN-MX-1U")
      (footprint "eagle-import:MX-1U")
      (libsource (lib "eagle-import") (part "KEYSWITCH-PLAIN-MX-1U"))
    )
    (comp (ref "MINUS")
      (value "KEYSWITCH-PLAIN-MX-1U")
      (footprint "eagle-import:MX-1U")
      (libsource (lib "eagle-import") (part "KEYSWITCH-PLAIN-MX-1U"))
    )
    (comp (ref "N")
      (value "KEYSWITCH-PLAIN-MX-1U")
      (footprint "eagle-import:MX-1U")
      (libsource (lib "eagle-import") (part "KEYSWITCH-PLAIN-MX-1U"))
    )
    (comp (ref "NUMPAD_0_BOTTOM")
      (value "KEYSWITCH-PLAIN-MX-1U")
      (footprint "eagle-import:MX-1U")
      (libsource (lib "eagle-import") (part "KEYSWITCH-PLAIN-MX-1U"))
    )
    (comp (ref "NUMPAD_0_FULL")
      (value "KEYSWITCH-PLAIN-MX-2U")
      (footprint "eagle-import:MX-2U")
      (libsource (lib "eagle-import") (part "KEYSWITCH-PLAIN-MX-2U"))
    )
    (comp (ref "NUMPAD_0_TOP")
      (value "KEYSWITCH-PLAIN-MX-1U")
      (footprint "eagle-import:MX-1U")
      (libsource (lib "eagle-import") (part "KEYSWITCH-PLAIN-MX-1U"))
    )
    (comp (ref "NUM_1")
      (value "KEYSWITCH-PLAIN-MX-1U")
      (footprint "eagle-import:MX-1U")
      (libsource (lib "eagle-import") (part "KEYSWITCH-PLAIN-MX-1U"))
    )
    (comp (ref "NUM_2")
      (value "KEYSWITCH-PLAIN-MX-1U")
      (footprint "eagle-import:MX-1U")
      (libsource (lib "eagle-import") (part "KEYSWITCH-PLAIN-MX-1U"))
    )
    (comp (ref "NUM_3")
      (value "KEYSWITCH-PLAIN-MX-1U")
      (footprint "eagle-import:MX-1U")
      (libsource (lib "eagle-import") (part "KEYSWITCH-PLAIN-MX-1U"))
    )
    (comp (ref "NUM_4")
      (value "KEYSWITCH-PLAIN-MX-1U")
      (footprint "eagle-import:MX-1U")
      (libsource (lib "eagle-import") (part "KEYSWITCH-PLAIN-MX-1U"))
    )
    (comp (ref "NUM_5")
      (value "KEYSWITCH-PLAIN-MX-1U")
      (footprint "eagle-import:MX-1U")
      (libsource (lib "eagle-import") (part "KEYSWITCH-PLAIN-MX-1U"))
    )
    (comp (ref "NUM_6")
      (value "KEYSWITCH-PLAIN-MX-1U")
      (footprint "eagle-import:MX-1U")
      (libsource (lib "eagle-import") (part "KEYSWITCH-PLAIN-MX-1U"))
    )
    (comp (ref "NUM_7")
      (value "KEYSWITCH-PLAIN-MX-1U")
      (footprint "eagle-import:MX-1U")
      (libsource (lib "eagle-import") (part "KEYSWITCH-PLAIN-MX-1U"))
    )
    (comp (ref "NUM_8")
      (value "KEYSWITCH-PLAIN-MX-1U")
      (footprint "eagle-import:MX-1U")
      (libsource (lib "eagle-import") (part "KEYSWITCH-PLAIN-MX-1U"))
    )
    (comp (ref "NUM_9")
      (value "KEYSWITCH-PLAIN-MX-1U")
      (footprint "eagle-import:MX-1U")
      (libsource (lib "eagle-import") (part "KEYSWITCH-PLAIN-MX-1U"))
    )
    (comp (ref "O")
      (value "KEYSWITCH-PLAIN-MX-1U")
      (footprint "eagle-import:MX-1U")
      (libsource (lib "eagle-import") (part "KEYSWITCH-PLAIN-MX-1U"))
    )
    (comp (ref "P")
      (value "KEYSWITCH-PLAIN-MX-1U")
      (footprint "eagle-import:MX-1U")
      (libsource (lib "eagle-import") (part "KEYSWITCH-PLAIN-MX-1U"))
    )
    (comp (ref "PASTE")
      (value "KEYSWITCH-PLAIN-MX-1U")
      (footprint "eagle-import:MX-1U")
      (libsource (lib "eagle-import") (part "KEYSWITCH-PLAIN-MX-1U"))
    )
    (comp (ref "PAUSE_BREAK")
      (value "KEYSWITCH-PLAIN-MX-1U")
      (footprint "eagle-import:MX-1U")
      (libsource (lib "eagle-import") (part "KEYSWITCH-PLAIN-MX-1U"))
    )
    (comp (ref "PERCENT")
      (value "KEYSWITCH-PLAIN-MX-1U")
      (footprint "eagle-import:MX-1U")
      (libsource (lib "eagle-import") (part "KEYSWITCH-PLAIN-MX-1U"))
    )
    (comp (ref "PERIOD")
      (value "KEYSWITCH-PLAIN-MX-1U")
      (footprint "eagle-import:MX-1U")
      (libsource (lib "eagle-import") (part "KEYSWITCH-PLAIN-MX-1U"))
    )
    (comp (ref "PG_DOWN")
      (value "KEYSWITCH-PLAIN-MX-1U")
      (footprint "eagle-import:MX-1U")
      (libsource (lib "eagle-import") (part "KEYSWITCH-PLAIN-MX-1U"))
    )
    (comp (ref "PG_UP")
      (value "KEYSWITCH-PLAIN-MX-1U")
      (footprint "eagle-import:MX-1U")
      (libsource (lib "eagle-import") (part "KEYSWITCH-PLAIN-MX-1U"))
    )
    (comp (ref "PIPE")
      (value "KEYSWITCH-PLAIN-MX-1U")
      (footprint "eagle-import:MX-1U")
      (libsource (lib "eagle-import") (part "KEYSWITCH-PLAIN-MX-1U"))
    )
    (comp (ref "PLUS")
      (value "KEYSWITCH-PLAIN-MX-1U")
      (footprint "eagle-import:MX-1U")
      (libsource (lib "eagle-import") (part "KEYSWITCH-PLAIN-MX-1U"))
    )
    (comp (ref "PRINT_SCREEN")
      (value "KEYSWITCH-PLAIN-MX-1U")
      (footprint "eagle-import:MX-1U")
      (libsource (lib "eagle-import") (part "KEYSWITCH-PLAIN-MX-1U"))
    )
    (comp (ref "Q")
      (value "KEYSWITCH-PLAIN-MX-1U")
      (footprint "eagle-import:MX-1U")
      (libsource (lib "eagle-import") (part "KEYSWITCH-PLAIN-MX-1U"))
    )
    (comp (ref "QUESTION_MARK")
      (value "KEYSWITCH-PLAIN-MX-1U")
      (footprint "eagle-import:MX-1U")
      (libsource (lib "eagle-import") (part "KEYSWITCH-PLAIN-MX-1U"))
    )
    (comp (ref "R")
      (value "KEYSWITCH-PLAIN-MX-1U")
      (footprint "eagle-import:MX-1U")
      (libsource (lib "eagle-import") (part "KEYSWITCH-PLAIN-MX-1U"))
    )
    (comp (ref "RIGHT")
      (value "KEYSWITCH-PLAIN-MX-1U")
      (footprint "eagle-import:MX-1U")
      (libsource (lib "eagle-import") (part "KEYSWITCH-PLAIN-MX-1U"))
    )
    (comp (ref "RIGHT_BRACKET")
      (value "KEYSWITCH-PLAIN-MX-1U")
      (footprint "eagle-import:MX-1U")
      (libsource (lib "eagle-import") (part "KEYSWITCH-PLAIN-MX-1U"))
    )
    (comp (ref "RIGHT_CBRACE")
      (value "KEYSWITCH-PLAIN-MX-1U")
      (footprint "eagle-import:MX-1U")
      (libsource (lib "eagle-import") (part "KEYSWITCH-PLAIN-MX-1U"))
    )
    (comp (ref "RIGHT_PAREN")
      (value "KEYSWITCH-PLAIN-MX-1U")
      (footprint "eagle-import:MX-1U")
      (libsource (lib "eagle-import") (part "KEYSWITCH-PLAIN-MX-1U"))
    )
    (comp (ref "RL_SPACE")
      (value "KEYSWITCH-PLAIN-MX-1U")
      (footprint "eagle-import:MX-1U")
      (libsource (lib "eagle-import") (part "KEYSWITCH-PLAIN-MX-1U"))
    )
    (comp (ref "RR_SPACE")
      (value "KEYSWITCH-PLAIN-MX-1U")
      (footprint "eagle-import:MX-1U")
      (libsource (lib "eagle-import") (part "KEYSWITCH-PLAIN-MX-1U"))
    )
    (comp (ref "R_SHIFT")
      (value "KEYSWITCH-PLAIN-MX-1U")
      (footprint "eagle-import:MX-1U")
      (libsource (lib "eagle-import") (part "KEYSWITCH-PLAIN-MX-1U"))
    )
    (comp (ref "R_SPACE")
      (value "KEYSWITCH-PLAIN-MX-2U")
      (footprint "eagle-import:MX-2U")
      (libsource (lib "eagle-import") (part "KEYSWITCH-PLAIN-MX-2U"))
    )
    (comp (ref "S")
      (value "KEYSWITCH-PLAIN-MX-1U")
      (footprint "eagle-import:MX-1U")
      (libsource (lib "eagle-import") (part "KEYSWITCH-PLAIN-MX-1U"))
    )
    (comp (ref "SCROLL_LOCK")
      (value "KEYSWITCH-PLAIN-MX-1U")
      (footprint "eagle-import:MX-1U")
      (libsource (lib "eagle-import") (part "KEYSWITCH-PLAIN-MX-1U"))
    )
    (comp (ref "SEMICOLON")
      (value "KEYSWITCH-PLAIN-MX-1U")
      (footprint "eagle-import:MX-1U")
      (libsource (lib "eagle-import") (part "KEYSWITCH-PLAIN-MX-1U"))
    )
    (comp (ref "SINGLE_QUOTE")
      (value "KEYSWITCH-PLAIN-MX-1U")
      (footprint "eagle-import:MX-1U")
      (libsource (lib "eagle-import") (part "KEYSWITCH-PLAIN-MX-1U"))
    )
    (comp (ref "T")
      (value "KEYSWITCH-PLAIN-MX-1U")
      (footprint "eagle-import:MX-1U")
      (libsource (lib "eagle-import") (part "KEYSWITCH-PLAIN-MX-1U"))
    )
    (comp (ref "TAB")
      (value "KEYSWITCH-PLAIN-MX-1U")
      (footprint "eagle-import:MX-1U")
      (libsource (lib "eagle-import") (part "KEYSWITCH-PLAIN-MX-1U"))
    )
    (comp (ref "TILDE")
      (value "KEYSWITCH-PLAIN-MX-1U")
      (footprint "eagle-import:MX-1U")
      (libsource (lib "eagle-import") (part "KEYSWITCH-PLAIN-MX-1U"))
    )
    (comp (ref "U")
      (value "KEYSWITCH-PLAIN-MX-1U")
      (footprint "eagle-import:MX-1U")
      (libsource (lib "eagle-import") (part "KEYSWITCH-PLAIN-MX-1U"))
    )
    (comp (ref "U$1")
      (value "HEADER-8X1-2.54")
      (footprint "eagle-import:HEADER-8X1-2.54")
      (libsource (lib "eagle-import") (part "HEADER-8X1-2.54"))
    )
    (comp (ref "U$2")
      (value "HEADER-8X1-2.54")
      (footprint "eagle-import:HEADER-8X1-2.54")
      (libsource (lib "eagle-import") (part "HEADER-8X1-2.54"))
    )
    (comp (ref "UNDESCORE")
      (value "KEYSWITCH-PLAIN-MX-1U")
      (footprint "eagle-import:MX-1U")
      (libsource (lib "eagle-import") (part "KEYSWITCH-PLAIN-MX-1U"))
    )
    (comp (ref "UP")
      (value "KEYSWITCH-PLAIN-MX-1U")
      (footprint "eagle-import:MX-1U")
      (libsource (lib "eagle-import") (part "KEYSWITCH-PLAIN-MX-1U"))
    )
    (comp (ref "V")
      (value "KEYSWITCH-PLAIN-MX-1U")
      (footprint "eagle-import:MX-1U")
      (libsource (lib "eagle-import") (part "KEYSWITCH-PLAIN-MX-1U"))
    )
    (comp (ref "W")
      (value "KEYSWITCH-PLAIN-MX-1U")
      (footprint "eagle-import:MX-1U")
      (libsource (lib "eagle-import") (part "KEYSWITCH-PLAIN-MX-1U"))
    )
    (comp (ref "X")
      (value "KEYSWITCH-PLAIN-MX-1U")
      (footprint "eagle-import:MX-1U")
      (libsource (lib "eagle-import") (part "KEYSWITCH-PLAIN-MX-1U"))
    )
    (comp (ref "Y")
      (value "KEYSWITCH-PLAIN-MX-1U")
      (footprint "eagle-import:MX-1U")
      (libsource (lib "eagle-import") (part "KEYSWITCH-PLAIN-MX-1U"))
    )
    (comp (ref "Z")
      (value "KEYSWITCH-PLAIN-MX-1U")
      (footprint "eagle-import:MX-1U")
      (libsource (lib "eagle-import") (part "KEYSWITCH-PLAIN-MX-1U"))
    )
  )
  (nets
    (net (code "1") (name "/C0") (class "Default")
      (node (ref "CUT") (pin "MX2") (pinfunction "P1_MX2") (pintype "bidirectional"))
      (node (ref "F1") (pin "MX2") (pinfunction "P1_MX2") (pintype "bidirectional"))
      (node (ref "F2") (pin "MX2") (pinfunction "P1_MX2") (pintype "bidirectional"))
      (node (ref "F3") (pin "MX2") (pinfunction "P1_MX2") (pintype "bidirectional"))
      (node (ref "F4") (pin "MX2") (pinfunction "P1_MX2") (pintype "bidirectional"))
      (node (ref "PRINT_SCREEN") (pin "MX2") (pinfunction "P1_MX2") (pintype "bidirectional"))
      (node (ref "U$2") (pin "8") (pinfunction "8_8") (pintype "bidirectional"))
    )
    (net (code "2") (name "/C1") (class "Default")
      (node (ref "COPY") (pin "MX2") (pinfunction "P1_MX2") (pintype "bidirectional"))
      (node (ref "F5") (pin "MX2") (pinfunction "P1_MX2") (pintype "bidirectional"))
      (node (ref "F6") (pin "MX2") (pinfunction "P1_MX2") (pintype "bidirectional"))
      (node (ref "F7") (pin "MX2") (pinfunction "P1_MX2") (pintype "bidirectional"))
      (node (ref "F8") (pin "MX2") (pinfunction "P1_MX2") (pintype "bidirectional"))
      (node (ref "J1") (pin "10") (pinfunction "10_10") (pintype "bidirectional"))
      (node (ref "SCROLL_LOCK") (pin "MX2") (pinfunction "P1_MX2") (pintype "bidirectional"))
    )
    (net (code "3") (name "/C2") (class "Default")
      (node (ref "F10") (pin "MX2") (pinfunction "P1_MX2") (pintype "bidirectional"))
      (node (ref "F11") (pin "MX2") (pinfunction "P1_MX2") (pintype "bidirectional"))
      (node (ref "F12") (pin "MX2") (pinfunction "P1_MX2") (pintype "bidirectional"))
      (node (ref "F9") (pin "MX2") (pinfunction "P1_MX2") (pintype "bidirectional"))
      (node (ref "PASTE") (pin "MX2") (pinfunction "P1_MX2") (pintype "bidirectional"))
      (node (ref "PAUSE_BREAK") (pin "MX2") (pinfunction "P1_MX2") (pintype "bidirectional"))
      (node (ref "U$1") (pin "8") (pinfunction "8_8") (pintype "bidirectional"))
    )
    (net (code "4") (name "/C3") (class "Default")
      (node (ref "CAPS_LOCK") (pin "MX2") (pinfunction "P1_MX2") (pintype "bidirectional"))
      (node (ref "ESCAPE") (pin "MX2") (pinfunction "P1_MX2") (pintype "bidirectional"))
      (node (ref "L_CTRL") (pin "MX2") (pinfunction "P1_MX2") (pintype "bidirectional"))
      (node (ref "L_SHIFT") (pin "MX2") (pinfunction "P1_MX2") (pintype "bidirectional"))
      (node (ref "TAB") (pin "MX2") (pinfunction "P1_MX2") (pintype "bidirectional"))
      (node (ref "TILDE") (pin "MX2") (pinfunction "P1_MX2") (pintype "bidirectional"))
      (node (ref "U$1") (pin "7") (pinfunction "7_7") (pintype "bidirectional"))
    )
    (net (code "5") (name "/C4") (class "Default")
      (node (ref "1") (pin "MX2") (pinfunction "P1_MX2") (pintype "bidirectional"))
      (node (ref "A") (pin "MX2") (pinfunction "P1_MX2") (pintype "bidirectional"))
      (node (ref "EXCLAMATION") (pin "MX2") (pinfunction "P1_MX2") (pintype "bidirectional"))
      (node (ref "L_WIN") (pin "MX2") (pinfunction "P1_MX2") (pintype "bidirectional"))
      (node (ref "Q") (pin "MX2") (pinfunction "P1_MX2") (pintype "bidirectional"))
      (node (ref "U$1") (pin "6") (pinfunction "6_6") (pintype "bidirectional"))
      (node (ref "Z") (pin "MX2") (pinfunction "P1_MX2") (pintype "bidirectional"))
    )
    (net (code "6") (name "/C5") (class "Default")
      (node (ref "2") (pin "MX2") (pinfunction "P1_MX2") (pintype "bidirectional"))
      (node (ref "AT") (pin "MX2") (pinfunction "P1_MX2") (pintype "bidirectional"))
      (node (ref "L_ALT") (pin "MX2") (pinfunction "P1_MX2") (pintype "bidirectional"))
      (node (ref "L_SPACE1") (pin "MX2") (pinfunction "P1_MX2") (pintype "bidirectional"))
      (node (ref "S") (pin "MX2") (pinfunction "P1_MX2") (pintype "bidirectional"))
      (node (ref "U$1") (pin "5") (pinfunction "5_5") (pintype "bidirectional"))
      (node (ref "W") (pin "MX2") (pinfunction "P1_MX2") (pintype "bidirectional"))
      (node (ref "X") (pin "MX2") (pinfunction "P1_MX2") (pintype "bidirectional"))
    )
    (net (code "7") (name "/C6") (class "Default")
      (node (ref "3") (pin "MX2") (pinfunction "P1_MX2") (pintype "bidirectional"))
      (node (ref "C") (pin "MX2") (pinfunction "P1_MX2") (pintype "bidirectional"))
      (node (ref "D") (pin "MX2") (pinfunction "P1_MX2") (pintype "bidirectional"))
      (node (ref "E") (pin "MX2") (pinfunction "P1_MX2") (pintype "bidirectional"))
      (node (ref "HASH") (pin "MX2") (pinfunction "P1_MX2") (pintype "bidirectional"))
      (node (ref "LL_SPACE") (pin "MX2") (pinfunction "P1_MX2") (pintype "bidirectional"))
      (node (ref "L_SPACE") (pin "MX2") (pinfunction "P1_MX2") (pintype "bidirectional"))
      (node (ref "U$1") (pin "4") (pinfunction "4_4") (pintype "bidirectional"))
    )
    (net (code "8") (name "/C7") (class "Default")
      (node (ref "4") (pin "MX2") (pinfunction "P1_MX2") (pintype "bidirectional"))
      (node (ref "DOLLAR") (pin "MX2") (pinfunction "P1_MX2") (pintype "bidirectional"))
      (node (ref "F") (pin "MX2") (pinfunction "P1_MX2") (pintype "bidirectional"))
      (node (ref "LR_SPACE") (pin "MX2") (pinfunction "P1_MX2") (pintype "bidirectional"))
      (node (ref "R") (pin "MX2") (pinfunction "P1_MX2") (pintype "bidirectional"))
      (node (ref "U$1") (pin "3") (pinfunction "3_3") (pintype "bidirectional"))
      (node (ref "V") (pin "MX2") (pinfunction "P1_MX2") (pintype "bidirectional"))
    )
    (net (code "9") (name "/C8") (class "Default")
      (node (ref "5") (pin "MX2") (pinfunction "P1_MX2") (pintype "bidirectional"))
      (node (ref "B") (pin "MX2") (pinfunction "P1_MX2") (pintype "bidirectional"))
      (node (ref "FN") (pin "MX2") (pinfunction "P1_MX2") (pintype "bidirectional"))
      (node (ref "G") (pin "MX2") (pinfunction "P1_MX2") (pintype "bidirectional"))
      (node (ref "L_SPACE2") (pin "MX2") (pinfunction "P1_MX2") (pintype "bidirectional"))
      (node (ref "PERCENT") (pin "MX2") (pinfunction "P1_MX2") (pintype "bidirectional"))
      (node (ref "T") (pin "MX2") (pinfunction "P1_MX2") (pintype "bidirectional"))
      (node (ref "U$1") (pin "2") (pinfunction "2_2") (pintype "bidirectional"))
    )
    (net (code "10") (name "/C9") (class "Default")
      (node (ref "6") (pin "MX2") (pinfunction "P1_MX2") (pintype "bidirectional"))
      (node (ref "CARROT") (pin "MX2") (pinfunction "P1_MX2") (pintype "bidirectional"))
      (node (ref "H") (pin "MX2") (pinfunction "P1_MX2") (pintype "bidirectional"))
      (node (ref "J2") (pin "1") (pinfunction "1_1") (pintype "bidirectional"))
      (node (ref "N") (pin "MX2") (pinfunction "P1_MX2") (pintype "bidirectional"))
      (node (ref "RL_SPACE") (pin "MX2") (pinfunction "P1_MX2") (pintype "bidirectional"))
      (node (ref "R_SPACE") (pin "MX2") (pinfunction "P1_MX2") (pintype "bidirectional"))
      (node (ref "Y") (pin "MX2") (pinfunction "P1_MX2") (pintype "bidirectional"))
    )
    (net (code "11") (name "/C10") (class "Default")
      (node (ref "7") (pin "MX2") (pinfunction "P1_MX2") (pintype "bidirectional"))
      (node (ref "AMPERSAND") (pin "MX2") (pinfunction "P1_MX2") (pintype "bidirectional"))
      (node (ref "J") (pin "MX2") (pinfunction "P1_MX2") (pintype "bidirectional"))
      (node (ref "J2") (pin "2") (pinfunction "2_2") (pintype "bidirectional"))
      (node (ref "M") (pin "MX2") (pinfunction "P1_MX2") (pintype "bidirectional"))
      (node (ref "RR_SPACE") (pin "MX2") (pinfunction "P1_MX2") (pintype "bidirectional"))
      (node (ref "U") (pin "MX2") (pinfunction "P1_MX2") (pintype "bidirectional"))
    )
    (net (code "12") (name "/C11") (class "Default")
      (node (ref "8") (pin "MX2") (pinfunction "P1_MX2") (pintype "bidirectional"))
      (node (ref "ASTERICK") (pin "MX2") (pinfunction "P1_MX2") (pintype "bidirectional"))
      (node (ref "COMMA") (pin "MX2") (pinfunction "P1_MX2") (pintype "bidirectional"))
      (node (ref "I") (pin "MX2") (pinfunction "P1_MX2") (pintype "bidirectional"))
      (node (ref "J2") (pin "5") (pinfunction "5_5") (pintype "bidirectional"))
      (node (ref "K") (pin "MX2") (pinfunction "P1_MX2") (pintype "bidirectional"))
      (node (ref "LESS_THAN") (pin "MX2") (pinfunction "P1_MX2") (pintype "bidirectional"))
    )
    (net (code "13") (name "/C12") (class "Default")
      (node (ref "9") (pin "MX2") (pinfunction "P1_MX2") (pintype "bidirectional"))
      (node (ref "GREATER_THAN") (pin "MX2") (pinfunction "P1_MX2") (pintype "bidirectional"))
      (node (ref "J2") (pin "12") (pinfunction "12_12") (pintype "bidirectional"))
      (node (ref "L") (pin "MX2") (pinfunction "P1_MX2") (pintype "bidirectional"))
      (node (ref "LEFT_PAREN") (pin "MX2") (pinfunction "P1_MX2") (pintype "bidirectional"))
      (node (ref "O") (pin "MX2") (pinfunction "P1_MX2") (pintype "bidirectional"))
      (node (ref "PERIOD") (pin "MX2") (pinfunction "P1_MX2") (pintype "bidirectional"))
    )
    (net (code "14") (name "/C13") (class "Default")
      (node (ref "0") (pin "MX2") (pinfunction "P1_MX2") (pintype "bidirectional"))
      (node (ref "COLON") (pin "MX2") (pinfunction "P1_MX2") (pintype "bidirectional"))
      (node (ref "FRONT_SLASH") (pin "MX2") (pinfunction "P1_MX2") (pintype "bidirectional"))
      (node (ref "J2") (pin "11") (pinfunction "11_11") (pintype "bidirectional"))
      (node (ref "P") (pin "MX2") (pinfunction "P1_MX2") (pintype "bidirectional"))
      (node (ref "QUESTION_MARK") (pin "MX2") (pinfunction "P1_MX2") (pintype "bidirectional"))
      (node (ref "RIGHT_PAREN") (pin "MX2") (pinfunction "P1_MX2") (pintype "bidirectional"))
    )
    (net (code "15") (name "/C14") (class "Default")
      (node (ref "J2") (pin "10") (pinfunction "10_10") (pintype "bidirectional"))
      (node (ref "LEFT") (pin "MX2") (pinfunction "P1_MX2") (pintype "bidirectional"))
      (node (ref "LEFT_BRACKET") (pin "MX2") (pinfunction "P1_MX2") (pintype "bidirectional"))
      (node (ref "MINUS") (pin "MX2") (pinfunction "P1_MX2") (pintype "bidirectional"))
      (node (ref "R_SHIFT") (pin "MX2") (pinfunction "P1_MX2") (pintype "bidirectional"))
      (node (ref "SINGLE_QUOTE") (pin "MX2") (pinfunction "P1_MX2") (pintype "bidirectional"))
      (node (ref "UNDESCORE") (pin "MX2") (pinfunction "P1_MX2") (pintype "bidirectional"))
    )
    (net (code "16") (name "/C15") (class "Default")
      (node (ref "DOWN") (pin "MX2") (pinfunction "P1_MX2") (pintype "bidirectional"))
      (node (ref "ENTER") (pin "MX2") (pinfunction "P1_MX2") (pintype "bidirectional"))
      (node (ref "EQUALS") (pin "MX2") (pinfunction "P1_MX2") (pintype "bidirectional"))
      (node (ref "J2") (pin "9") (pinfunction "9_9") (pintype "bidirectional"))
      (node (ref "PLUS") (pin "MX2") (pinfunction "P1_MX2") (pintype "bidirectional"))
      (node (ref "RIGHT_BRACKET") (pin "MX2") (pinfunction "P1_MX2") (pintype "bidirectional"))
      (node (ref "UP") (pin "MX2") (pinfunction "P1_MX2") (pintype "bidirectional"))
    )
    (net (code "17") (name "/C16") (class "Default")
      (node (ref "BACKSPACE") (pin "MX2") (pinfunction "P1_MX2") (pintype "bidirectional"))
      (node (ref "BACK_SLASH") (pin "MX2") (pinfunction "P1_MX2") (pintype "bidirectional"))
      (node (ref "DELETE") (pin "MX2") (pinfunction "P1_MX2") (pintype "bidirectional"))
      (node (ref "J2") (pin "8") (pinfunction "8_8") (pintype "bidirectional"))
      (node (ref "NUMPAD_0_BOTTOM") (pin "MX2") (pinfunction "P1_MX2") (pintype "bidirectional"))
      (node (ref "NUMPAD_0_FULL") (pin "MX2") (pinfunction "P1_MX2") (pintype "bidirectional"))
      (node (ref "NUMPAD_0_TOP") (pin "MX2") (pinfunction "P1_MX2") (pintype "bidirectional"))
      (node (ref "RIGHT") (pin "MX2") (pinfunction "P1_MX2") (pintype "bidirectional"))
    )
    (net (code "18") (name "/C17") (class "Default")
      (node (ref "HOME") (pin "MX2") (pinfunction "P1_MX2") (pintype "bidirectional"))
      (node (ref "J2") (pin "7") (pinfunction "7_7") (pintype "bidirectional"))
      (node (ref "LEFT_CBRACE") (pin "MX2") (pinfunction "P1_MX2") (pintype "bidirectional"))
      (node (ref "NUM_1") (pin "MX2") (pinfunction "P1_MX2") (pintype "bidirectional"))
      (node (ref "NUM_4") (pin "MX2") (pinfunction "P1_MX2") (pintype "bidirectional"))
      (node (ref "NUM_7") (pin "MX2") (pinfunction "P1_MX2") (pintype "bidirectional"))
      (node (ref "SEMICOLON") (pin "MX2") (pinfunction "P1_MX2") (pintype "bidirectional"))
    )
    (net (code "19") (name "/C18") (class "Default")
      (node (ref "DBL_QUOTE") (pin "MX2") (pinfunction "P1_MX2") (pintype "bidirectional"))
      (node (ref "END") (pin "MX2") (pinfunction "P1_MX2") (pintype "bidirectional"))
      (node (ref "J2") (pin "6") (pinfunction "6_6") (pintype "bidirectional"))
      (node (ref "NUM_2") (pin "MX2") (pinfunction "P1_MX2") (pintype "bidirectional"))
      (node (ref "NUM_5") (pin "MX2") (pinfunction "P1_MX2") (pintype "bidirectional"))
      (node (ref "NUM_8") (pin "MX2") (pinfunction "P1_MX2") (pintype "bidirectional"))
      (node (ref "RIGHT_CBRACE") (pin "MX2") (pinfunction "P1_MX2") (pintype "bidirectional"))
    )
    (net (code "20") (name "/C19") (class "Default")
      (node (ref "J1") (pin "12") (pinfunction "12_12") (pintype "bidirectional"))
      (node (ref "NUM_3") (pin "MX2") (pinfunction "P1_MX2") (pintype "bidirectional"))
      (node (ref "NUM_6") (pin "MX2") (pinfunction "P1_MX2") (pintype "bidirectional"))
      (node (ref "NUM_9") (pin "MX2") (pinfunction "P1_MX2") (pintype "bidirectional"))
      (node (ref "PG_DOWN") (pin "MX2") (pinfunction "P1_MX2") (pintype "bidirectional"))
      (node (ref "PG_UP") (pin "MX2") (pinfunction "P1_MX2") (pintype "bidirectional"))
      (node (ref "PIPE") (pin "MX2") (pinfunction "P1_MX2") (pintype "bidirectional"))
    )
    (net (code "21") (name "/R0") (class "Default")
      (node (ref "D1") (pin "C") (pinfunction "C_C") (pintype "passive"))
      (node (ref "D10") (pin "C") (pinfunction "C_C") (pintype "passive"))
      (node (ref "D11") (pin "C") (pinfunction "C_C") (pintype "passive"))
      (node (ref "D12") (pin "C") (pinfunction "C_C") (pintype "passive"))
      (node (ref "D13") (pin "C") (pinfunction "C_C") (pintype "passive"))
      (node (ref "D14") (pin "C") (pinfunction "C_C") (pintype "passive"))
      (node (ref "D15") (pin "C") (pinfunction "C_C") (pintype "passive"))
      (node (ref "D16") (pin "C") (pinfunction "C_C") (pintype "passive"))
      (node (ref "D17") (pin "C") (pinfunction "C_C") (pintype "passive"))
      (node (ref "D18") (pin "C") (pinfunction "C_C") (pintype "passive"))
      (node (ref "D19") (pin "C") (pinfunction "C_C") (pintype "passive"))
      (node (ref "D2") (pin "C") (pinfunction "C_C") (pintype "passive"))
      (node (ref "D20") (pin "C") (pinfunction "C_C") (pintype "passive"))
      (node (ref "D3") (pin "C") (pinfunction "C_C") (pintype "passive"))
      (node (ref "D4") (pin "C") (pinfunction "C_C") (pintype "passive"))
      (node (ref "D5") (pin "C") (pinfunction "C_C") (pintype "passive"))
      (node (ref "D6") (pin "C") (pinfunction "C_C") (pintype "passive"))
      (node (ref "D7") (pin "C") (pinfunction "C_C") (pintype "passive"))
      (node (ref "D8") (pin "C") (pinfunction "C_C") (pintype "passive"))
      (node (ref "D9") (pin "C") (pinfunction "C_C") (pintype "passive"))
      (node (ref "U$2") (pin "2") (pinfunction "2_2") (pintype "bidirectional"))
    )
    (net (code "22") (name "/R1") (class "Default")
      (node (ref "D21") (pin "C") (pinfunction "C_C") (pintype "passive"))
      (node (ref "D22") (pin "C") (pinfunction "C_C") (pintype "passive"))
      (node (ref "D23") (pin "C") (pinfunction "C_C") (pintype "passive"))
      (node (ref "D24") (pin "C") (pinfunction "C_C") (pintype "passive"))
      (node (ref "D25") (pin "C") (pinfunction "C_C") (pintype "passive"))
      (node (ref "D26") (pin "C") (pinfunction "C_C") (pintype "passive"))
      (node (ref "D27") (pin "C") (pinfunction "C_C") (pintype "passive"))
      (node (ref "D28") (pin "C") (pinfunction "C_C") (pintype "passive"))
      (node (ref "D29") (pin "C") (pinfunction "C_C") (pintype "passive"))
      (node (ref "D30") (pin "C") (pinfunction "C_C") (pintype "passive"))
      (node (ref "D31") (pin "C") (pinfunction "C_C") (pintype "passive"))
      (node (ref "D32") (pin "C") (pinfunction "C_C") (pintype "passive"))
      (node (ref "D33") (pin "C") (pinfunction "C_C") (pintype "passive"))
      (node (ref "D34") (pin "C") (pinfunction "C_C") (pintype "passive"))
      (node (ref "D35") (pin "C") (pinfunction "C_C") (pintype "passive"))
      (node (ref "D36") (pin "C") (pinfunction "C_C") (pintype "passive"))
      (node (ref "D37") (pin "C") (pinfunction "C_C") (pintype "passive"))
      (node (ref "D38") (pin "C") (pinfunction "C_C") (pintype "passive"))
      (node (ref "D39") (pin "C") (pinfunction "C_C") (pintype "passive"))
      (node (ref "D40") (pin "C") (pinfunction "C_C") (pintype "passive"))
      (node (ref "U$2") (pin "3") (pinfunction "3_3") (pintype "bidirectional"))
    )
    (net (code "23") (name "/R2") (class "Default")
      (node (ref "D41") (pin "C") (pinfunction "C_C") (pintype "passive"))
      (node (ref "D42") (pin "C") (pinfunction "C_C") (pintype "passive"))
      (node (ref "D43") (pin "C") (pinfunction "C_C") (pintype "passive"))
      (node (ref "D44") (pin "C") (pinfunction "C_C") (pintype "passive"))
      (node (ref "D45") (pin "C") (pinfunction "C_C") (pintype "passive"))
      (node (ref "D46") (pin "C") (pinfunction "C_C") (pintype "passive"))
      (node (ref "D47") (pin "C") (pinfunction "C_C") (pintype "passive"))
      (node (ref "D48") (pin "C") (pinfunction "C_C") (pintype "passive"))
      (node (ref "D49") (pin "C") (pinfunction "C_C") (pintype "passive"))
      (node (ref "D50") (pin "C") (pinfunction "C_C") (pintype "passive"))
      (node (ref "D51") (pin "C") (pinfunction "C_C") (pintype "passive"))
      (node (ref "D52") (pin "C") (pinfunction "C_C") (pintype "passive"))
      (node (ref "D53") (pin "C") (pinfunction "C_C") (pintype "passive"))
      (node (ref "D54") (pin "C") (pinfunction "C_C") (pintype "passive"))
      (node (ref "D55") (pin "C") (pinfunction "C_C") (pintype "passive"))
      (node (ref "D56") (pin "C") (pinfunction "C_C") (pintype "passive"))
      (node (ref "D57") (pin "C") (pinfunction "C_C") (pintype "passive"))
      (node (ref "D58") (pin "C") (pinfunction "C_C") (pintype "passive"))
      (node (ref "D59") (pin "C") (pinfunction "C_C") (pintype "passive"))
      (node (ref "D60") (pin "C") (pinfunction "C_C") (pintype "passive"))
      (node (ref "U$2") (pin "4") (pinfunction "4_4") (pintype "bidirectional"))
    )
    (net (code "24") (name "/R3") (class "Default")
      (node (ref "D61") (pin "C") (pinfunction "C_C") (pintype "passive"))
      (node (ref "D62") (pin "C") (pinfunction "C_C") (pintype "passive"))
      (node (ref "D63") (pin "C") (pinfunction "C_C") (pintype "passive"))
      (node (ref "D64") (pin "C") (pinfunction "C_C") (pintype "passive"))
      (node (ref "D65") (pin "C") (pinfunction "C_C") (pintype "passive"))
      (node (ref "D66") (pin "C") (pinfunction "C_C") (pintype "passive"))
      (node (ref "D67") (pin "C") (pinfunction "C_C") (pintype "passive"))
      (node (ref "D68") (pin "C") (pinfunction "C_C") (pintype "passive"))
      (node (ref "D69") (pin "C") (pinfunction "C_C") (pintype "passive"))
      (node (ref "D70") (pin "C") (pinfunction "C_C") (pintype "passive"))
      (node (ref "D71") (pin "C") (pinfunction "C_C") (pintype "passive"))
      (node (ref "D72") (pin "C") (pinfunction "C_C") (pintype "passive"))
      (node (ref "D73") (pin "C") (pinfunction "C_C") (pintype "passive"))
      (node (ref "D74") (pin "C") (pinfunction "C_C") (pintype "passive"))
      (node (ref "D75") (pin "C") (pinfunction "C_C") (pintype "passive"))
      (node (ref "D76") (pin "C") (pinfunction "C_C") (pintype "passive"))
      (node (ref "D77") (pin "C") (pinfunction "C_C") (pintype "passive"))
      (node (ref "D78") (pin "C") (pinfunction "C_C") (pintype "passive"))
      (node (ref "D79") (pin "C") (pinfunction "C_C") (pintype "passive"))
      (node (ref "D80") (pin "C") (pinfunction "C_C") (pintype "passive"))
      (node (ref "U$2") (pin "5") (pinfunction "5_5") (pintype "bidirectional"))
    )
    (net (code "25") (name "/R4") (class "Default")
      (node (ref "D100") (pin "C") (pinfunction "C_C") (pintype "passive"))
      (node (ref "D81") (pin "C") (pinfunction "C_C") (pintype "passive"))
      (node (ref "D82") (pin "C") (pinfunction "C_C") (pintype "passive"))
      (node (ref "D83") (pin "C") (pinfunction "C_C") (pintype "passive"))
      (node (ref "D84") (pin "C") (pinfunction "C_C") (pintype "passive"))
      (node (ref "D85") (pin "C") (pinfunction "C_C") (pintype "passive"))
      (node (ref "D86") (pin "C") (pinfunction "C_C") (pintype "passive"))
      (node (ref "D87") (pin "C") (pinfunction "C_C") (pintype "passive"))
      (node (ref "D88") (pin "C") (pinfunction "C_C") (pintype "passive"))
      (node (ref "D89") (pin "C") (pinfunction "C_C") (pintype "passive"))
      (node (ref "D90") (pin "C") (pinfunction "C_C") (pintype "passive"))
      (node (ref "D91") (pin "C") (pinfunction "C_C") (pintype "passive"))
      (node (ref "D92") (pin "C") (pinfunction "C_C") (pintype "passive"))
      (node (ref "D93") (pin "C") (pinfunction "C_C") (pintype "passive"))
      (node (ref "D94") (pin "C") (pinfunction "C_C") (pintype "passive"))
      (node (ref "D95") (pin "C") (pinfunction "C_C") (pintype "passive"))
      (node (ref "D96") (pin "C") (pinfunction "C_C") (pintype "passive"))
      (node (ref "D97") (pin "C") (pinfunction "C_C") (pintype "passive"))
      (node (ref "D98") (pin "C") (pinfunction "C_C") (pintype "passive"))
      (node (ref "D99") (pin "C") (pinfunction "C_C") (pintype "passive"))
      (node (ref "U$2") (pin "6") (pinfunction "6_6") (pintype "bidirectional"))
    )
    (net (code "26") (name "/R5") (class "Default")
      (node (ref "D101") (pin "C") (pinfunction "C_C") (pintype "passive"))
      (node (ref "D102") (pin "C") (pinfunction "C_C") (pintype "passive"))
      (node (ref "D103") (pin "C") (pinfunction "C_C") (pintype "passive"))
      (node (ref "D104") (pin "C") (pinfunction "C_C") (pintype "passive"))
      (node (ref "D105") (pin "C") (pinfunction "C_C") (pintype "passive"))
      (node (ref "D106") (pin "C") (pinfunction "C_C") (pintype "passive"))
      (node (ref "D107") (pin "C") (pinfunction "C_C") (pintype "passive"))
      (node (ref "D108") (pin "C") (pinfunction "C_C") (pintype "passive"))
      (node (ref "D109") (pin "C") (pinfunction "C_C") (pintype "passive"))
      (node (ref "D110") (pin "C") (pinfunction "C_C") (pintype "passive"))
      (node (ref "D111") (pin "C") (pinfunction "C_C") (pintype "passive"))
      (node (ref "D112") (pin "C") (pinfunction "C_C") (pintype "passive"))
      (node (ref "D113") (pin "C") (pinfunction "C_C") (pintype "passive"))
      (node (ref "D114") (pin "C") (pinfunction "C_C") (pintype "passive"))
      (node (ref "D115") (pin "C") (pinfunction "C_C") (pintype "passive"))
      (node (ref "D116") (pin "C") (pinfunction "C_C") (pintype "passive"))
      (node (ref "D117") (pin "C") (pinfunction "C_C") (pintype "passive"))
      (node (ref "D118") (pin "C") (pinfunction "C_C") (pintype "passive"))
      (node (ref "D119") (pin "C") (pinfunction "C_C") (pintype "passive"))
      (node (ref "D120") (pin "C") (pinfunction "C_C") (pintype "passive"))
      (node (ref "U$2") (pin "7") (pinfunction "7_7") (pintype "bidirectional"))
    )
    (net (code "27") (name "GND") (class "Default")
      (node (ref "J2") (pin "3") (pinfunction "3_3") (pintype "bidirectional"))
      (node (ref "U$2") (pin "1") (pinfunction "1_1") (pintype "bidirectional"))
    )
    (net (code "28") (name "Net-(0-P0)") (class "Default")
      (node (ref "0") (pin "MX1") (pinfunction "P0_MX1") (pintype "bidirectional"))
      (node (ref "D34") (pin "A") (pinfunction "A_A") (pintype "passive"))
    )
    (net (code "29") (name "Net-(1-P0)") (class "Default")
      (node (ref "1") (pin "MX1") (pinfunction "P0_MX1") (pintype "bidirectional"))
      (node (ref "D25") (pin "A") (pinfunction "A_A") (pintype "passive"))
    )
    (net (code "30") (name "Net-(2-P0)") (class "Default")
      (node (ref "2") (pin "MX1") (pinfunction "P0_MX1") (pintype "bidirectional"))
      (node (ref "D26") (pin "A") (pinfunction "A_A") (pintype "passive"))
    )
    (net (code "31") (name "Net-(3-P0)") (class "Default")
      (node (ref "3") (pin "MX1") (pinfunction "P0_MX1") (pintype "bidirectional"))
      (node (ref "D27") (pin "A") (pinfunction "A_A") (pintype "passive"))
    )
    (net (code "32") (name "Net-(4-P0)") (class "Default")
      (node (ref "4") (pin "MX1") (pinfunction "P0_MX1") (pintype "bidirectional"))
      (node (ref "D28") (pin "A") (pinfunction "A_A") (pintype "passive"))
    )
    (net (code "33") (name "Net-(5-P0)") (class "Default")
      (node (ref "5") (pin "MX1") (pinfunction "P0_MX1") (pintype "bidirectional"))
      (node (ref "D29") (pin "A") (pinfunction "A_A") (pintype "passive"))
    )
    (net (code "34") (name "Net-(6-P0)") (class "Default")
      (node (ref "6") (pin "MX1") (pinfunction "P0_MX1") (pintype "bidirectional"))
      (node (ref "D30") (pin "A") (pinfunction "A_A") (pintype "passive"))
    )
    (net (code "35") (name "Net-(7-P0)") (class "Default")
      (node (ref "7") (pin "MX1") (pinfunction "P0_MX1") (pintype "bidirectional"))
      (node (ref "D31") (pin "A") (pinfunction "A_A") (pintype "passive"))
    )
    (net (code "36") (name "Net-(8-P0)") (class "Default")
      (node (ref "8") (pin "MX1") (pinfunction "P0_MX1") (pintype "bidirectional"))
      (node (ref "D32") (pin "A") (pinfunction "A_A") (pintype "passive"))
    )
    (net (code "37") (name "Net-(9-P0)") (class "Default")
      (node (ref "9") (pin "MX1") (pinfunction "P0_MX1") (pintype "bidirectional"))
      (node (ref "D33") (pin "A") (pinfunction "A_A") (pintype "passive"))
    )
    (net (code "38") (name "Net-(A-P0)") (class "Default")
      (node (ref "A") (pin "MX1") (pinfunction "P0_MX1") (pintype "bidirectional"))
      (node (ref "D65") (pin "A") (pinfunction "A_A") (pintype "passive"))
    )
    (net (code "39") (name "Net-(AMPERSAND-P0)") (class "Default")
      (node (ref "AMPERSAND") (pin "MX1") (pinfunction "P0_MX1") (pintype "bidirectional"))
      (node (ref "D11") (pin "A") (pinfunction "A_A") (pintype "passive"))
    )
    (net (code "40") (name "Net-(ASTERICK-P0)") (class "Default")
      (node (ref "ASTERICK") (pin "MX1") (pinfunction "P0_MX1") (pintype "bidirectional"))
      (node (ref "D12") (pin "A") (pinfunction "A_A") (pintype "passive"))
    )
    (net (code "41") (name "Net-(AT-P0)") (class "Default")
      (node (ref "AT") (pin "MX1") (pinfunction "P0_MX1") (pintype "bidirectional"))
      (node (ref "D6") (pin "A") (pinfunction "A_A") (pintype "passive"))
    )
    (net (code "42") (name "Net-(B-P0)") (class "Default")
      (node (ref "B") (pin "MX1") (pinfunction "P0_MX1") (pintype "bidirectional"))
      (node (ref "D89") (pin "A") (pinfunction "A_A") (pintype "passive"))
    )
    (net (code "43") (name "Net-(BACKSPACE-P0)") (class "Default")
      (node (ref "BACKSPACE") (pin "MX1") (pinfunction "P0_MX1") (pintype "bidirectional"))
      (node (ref "D37") (pin "A") (pinfunction "A_A") (pintype "passive"))
    )
    (net (code "44") (name "Net-(BACK_SLASH-P0)") (class "Default")
      (node (ref "BACK_SLASH") (pin "MX1") (pinfunction "P0_MX1") (pintype "bidirectional"))
      (node (ref "D57") (pin "A") (pinfunction "A_A") (pintype "passive"))
    )
    (net (code "45") (name "Net-(C-P0)") (class "Default")
      (node (ref "C") (pin "MX1") (pinfunction "P0_MX1") (pintype "bidirectional"))
      (node (ref "D87") (pin "A") (pinfunction "A_A") (pintype "passive"))
    )
    (net (code "46") (name "Net-(CAPS_LOCK-P0)") (class "Default")
      (node (ref "CAPS_LOCK") (pin "MX1") (pinfunction "P0_MX1") (pintype "bidirectional"))
      (node (ref "D64") (pin "A") (pinfunction "A_A") (pintype "passive"))
    )
    (net (code "47") (name "Net-(CARROT-P0)") (class "Default")
      (node (ref "CARROT") (pin "MX1") (pinfunction "P0_MX1") (pintype "bidirectional"))
      (node (ref "D10") (pin "A") (pinfunction "A_A") (pintype "passive"))
    )
    (net (code "48") (name "Net-(COLON-P0)") (class "Default")
      (node (ref "COLON") (pin "MX1") (pinfunction "P0_MX1") (pintype "bidirectional"))
      (node (ref "D74") (pin "A") (pinfunction "A_A") (pintype "passive"))
    )
    (net (code "49") (name "Net-(COMMA-P0)") (class "Default")
      (node (ref "COMMA") (pin "MX1") (pinfunction "P0_MX1") (pintype "bidirectional"))
      (node (ref "D112") (pin "A") (pinfunction "A_A") (pintype "passive"))
    )
    (net (code "50") (name "Net-(COPY-P0)") (class "Default")
      (node (ref "COPY") (pin "MX1") (pinfunction "P0_MX1") (pintype "bidirectional"))
      (node (ref "D102") (pin "A") (pinfunction "A_A") (pintype "passive"))
    )
    (net (code "51") (name "Net-(CUT-P0)") (class "Default")
      (node (ref "CUT") (pin "MX1") (pinfunction "P0_MX1") (pintype "bidirectional"))
      (node (ref "D101") (pin "A") (pinfunction "A_A") (pintype "passive"))
    )
    (net (code "52") (name "Net-(D-P0)") (class "Default")
      (node (ref "D") (pin "MX1") (pinfunction "P0_MX1") (pintype "bidirectional"))
      (node (ref "D67") (pin "A") (pinfunction "A_A") (pintype "passive"))
    )
    (net (code "53") (name "Net-(DBL_QUOTE-P0)") (class "Default")
      (node (ref "D59") (pin "A") (pinfunction "A_A") (pintype "passive"))
      (node (ref "DBL_QUOTE") (pin "MX1") (pinfunction "P0_MX1") (pintype "bidirectional"))
    )
    (net (code "54") (name "Net-(DELETE-P0)") (class "Default")
      (node (ref "D17") (pin "A") (pinfunction "A_A") (pintype "passive"))
      (node (ref "DELETE") (pin "MX1") (pinfunction "P0_MX1") (pintype "bidirectional"))
    )
    (net (code "55") (name "Net-(DOLLAR-P0)") (class "Default")
      (node (ref "D8") (pin "A") (pinfunction "A_A") (pintype "passive"))
      (node (ref "DOLLAR") (pin "MX1") (pinfunction "P0_MX1") (pintype "bidirectional"))
    )
    (net (code "56") (name "Net-(DOWN-P0)") (class "Default")
      (node (ref "D116") (pin "A") (pinfunction "A_A") (pintype "passive"))
      (node (ref "DOWN") (pin "MX1") (pinfunction "P0_MX1") (pintype "bidirectional"))
    )
    (net (code "57") (name "Net-(E-P0)") (class "Default")
      (node (ref "D47") (pin "A") (pinfunction "A_A") (pintype "passive"))
      (node (ref "E") (pin "MX1") (pinfunction "P0_MX1") (pintype "bidirectional"))
    )
    (net (code "58") (name "Net-(END-P0)") (class "Default")
      (node (ref "D39") (pin "A") (pinfunction "A_A") (pintype "passive"))
      (node (ref "END") (pin "MX1") (pinfunction "P0_MX1") (pintype "bidirectional"))
    )
    (net (code "59") (name "Net-(ENTER-P0)") (class "Default")
      (node (ref "D76") (pin "A") (pinfunction "A_A") (pintype "passive"))
      (node (ref "ENTER") (pin "MX1") (pinfunction "P0_MX1") (pintype "bidirectional"))
    )
    (net (code "60") (name "Net-(EQUALS-P0)") (class "Default")
      (node (ref "D36") (pin "A") (pinfunction "A_A") (pintype "passive"))
      (node (ref "EQUALS") (pin "MX1") (pinfunction "P0_MX1") (pintype "bidirectional"))
    )
    (net (code "61") (name "Net-(ESCAPE-P0)") (class "Default")
      (node (ref "D24") (pin "A") (pinfunction "A_A") (pintype "passive"))
      (node (ref "ESCAPE") (pin "MX1") (pinfunction "P0_MX1") (pintype "bidirectional"))
    )
    (net (code "62") (name "Net-(EXCLAMATION-P0)") (class "Default")
      (node (ref "D5") (pin "A") (pinfunction "A_A") (pintype "passive"))
      (node (ref "EXCLAMATION") (pin "MX1") (pinfunction "P0_MX1") (pintype "bidirectional"))
    )
    (net (code "63") (name "Net-(F-P0)") (class "Default")
      (node (ref "D68") (pin "A") (pinfunction "A_A") (pintype "passive"))
      (node (ref "F") (pin "MX1") (pinfunction "P0_MX1") (pintype "bidirectional"))
    )
    (net (code "64") (name "Net-(F1-P0)") (class "Default")
      (node (ref "D61") (pin "A") (pinfunction "A_A") (pintype "passive"))
      (node (ref "F1") (pin "MX1") (pinfunction "P0_MX1") (pintype "bidirectional"))
    )
    (net (code "65") (name "Net-(F2-P0)") (class "Default")
      (node (ref "D41") (pin "A") (pinfunction "A_A") (pintype "passive"))
      (node (ref "F2") (pin "MX1") (pinfunction "P0_MX1") (pintype "bidirectional"))
    )
    (net (code "66") (name "Net-(F3-P0)") (class "Default")
      (node (ref "D21") (pin "A") (pinfunction "A_A") (pintype "passive"))
      (node (ref "F3") (pin "MX1") (pinfunction "P0_MX1") (pintype "bidirectional"))
    )
    (net (code "67") (name "Net-(F4-P0)") (class "Default")
      (node (ref "D1") (pin "A") (pinfunction "A_A") (pintype "passive"))
      (node (ref "F4") (pin "MX1") (pinfunction "P0_MX1") (pintype "bidirectional"))
    )
    (net (code "68") (name "Net-(F5-P0)") (class "Default")
      (node (ref "D62") (pin "A") (pinfunction "A_A") (pintype "passive"))
      (node (ref "F5") (pin "MX1") (pinfunction "P0_MX1") (pintype "bidirectional"))
    )
    (net (code "69") (name "Net-(F6-P0)") (class "Default")
      (node (ref "D42") (pin "A") (pinfunction "A_A") (pintype "passive"))
      (node (ref "F6") (pin "MX1") (pinfunction "P0_MX1") (pintype "bidirectional"))
    )
    (net (code "70") (name "Net-(F7-P0)") (class "Default")
      (node (ref "D22") (pin "A") (pinfunction "A_A") (pintype "passive"))
      (node (ref "F7") (pin "MX1") (pinfunction "P0_MX1") (pintype "bidirectional"))
    )
    (net (code "71") (name "Net-(F8-P0)") (class "Default")
      (node (ref "D2") (pin "A") (pinfunction "A_A") (pintype "passive"))
      (node (ref "F8") (pin "MX1") (pinfunction "P0_MX1") (pintype "bidirectional"))
    )
    (net (code "72") (name "Net-(F9-P0)") (class "Default")
      (node (ref "D63") (pin "A") (pinfunction "A_A") (pintype "passive"))
      (node (ref "F9") (pin "MX1") (pinfunction "P0_MX1") (pintype "bidirectional"))
    )
    (net (code "73") (name "Net-(F10-P0)") (class "Default")
      (node (ref "D43") (pin "A") (pinfunction "A_A") (pintype "passive"))
      (node (ref "F10") (pin "MX1") (pinfunction "P0_MX1") (pintype "bidirectional"))
    )
    (net (code "74") (name "Net-(F11-P0)") (class "Default")
      (node (ref "D23") (pin "A") (pinfunction "A_A") (pintype "passive"))
      (node (ref "F11") (pin "MX1") (pinfunction "P0_MX1") (pintype "bidirectional"))
    )
    (net (code "75") (name "Net-(F12-P0)") (class "Default")
      (node (ref "D3") (pin "A") (pinfunction "A_A") (pintype "passive"))
      (node (ref "F12") (pin "MX1") (pinfunction "P0_MX1") (pintype "bidirectional"))
    )
    (net (code "76") (name "Net-(FN-P0)") (class "Default")
      (node (ref "D109") (pin "A") (pinfunction "A_A") (pintype "passive"))
      (node (ref "FN") (pin "MX1") (pinfunction "P0_MX1") (pintype "bidirectional"))
      (node (ref "L_SPACE2") (pin "MX1") (pinfunction "P0_MX1") (pintype "bidirectional"))
    )
    (net (code "77") (name "Net-(FRONT_SLASH-P0)") (class "Default")
      (node (ref "D114") (pin "A") (pinfunction "A_A") (pintype "passive"))
      (node (ref "FRONT_SLASH") (pin "MX1") (pinfunction "P0_MX1") (pintype "bidirectional"))
    )
    (net (code "78") (name "Net-(G-P0)") (class "Default")
      (node (ref "D69") (pin "A") (pinfunction "A_A") (pintype "passive"))
      (node (ref "G") (pin "MX1") (pinfunction "P0_MX1") (pintype "bidirectional"))
    )
    (net (code "79") (name "Net-(GREATER_THAN-P0)") (class "Default")
      (node (ref "D93") (pin "A") (pinfunction "A_A") (pintype "passive"))
      (node (ref "GREATER_THAN") (pin "MX1") (pinfunction "P0_MX1") (pintype "bidirectional"))
    )
    (net (code "80") (name "Net-(H-P0)") (class "Default")
      (node (ref "D70") (pin "A") (pinfunction "A_A") (pintype "passive"))
      (node (ref "H") (pin "MX1") (pinfunction "P0_MX1") (pintype "bidirectional"))
    )
    (net (code "81") (name "Net-(HASH-P0)") (class "Default")
      (node (ref "D7") (pin "A") (pinfunction "A_A") (pintype "passive"))
      (node (ref "HASH") (pin "MX1") (pinfunction "P0_MX1") (pintype "bidirectional"))
    )
    (net (code "82") (name "Net-(HOME-P0)") (class "Default")
      (node (ref "D38") (pin "A") (pinfunction "A_A") (pintype "passive"))
      (node (ref "HOME") (pin "MX1") (pinfunction "P0_MX1") (pintype "bidirectional"))
    )
    (net (code "83") (name "Net-(I-P0)") (class "Default")
      (node (ref "D52") (pin "A") (pinfunction "A_A") (pintype "passive"))
      (node (ref "I") (pin "MX1") (pinfunction "P0_MX1") (pintype "bidirectional"))
    )
    (net (code "84") (name "Net-(J-P0)") (class "Default")
      (node (ref "D71") (pin "A") (pinfunction "A_A") (pintype "passive"))
      (node (ref "J") (pin "MX1") (pinfunction "P0_MX1") (pintype "bidirectional"))
    )
    (net (code "85") (name "Net-(K-P0)") (class "Default")
      (node (ref "D72") (pin "A") (pinfunction "A_A") (pintype "passive"))
      (node (ref "K") (pin "MX1") (pinfunction "P0_MX1") (pintype "bidirectional"))
    )
    (net (code "86") (name "Net-(L-P0)") (class "Default")
      (node (ref "D73") (pin "A") (pinfunction "A_A") (pintype "passive"))
      (node (ref "L") (pin "MX1") (pinfunction "P0_MX1") (pintype "bidirectional"))
    )
    (net (code "87") (name "Net-(LEFT-P0)") (class "Default")
      (node (ref "D115") (pin "A") (pinfunction "A_A") (pintype "passive"))
      (node (ref "LEFT") (pin "MX1") (pinfunction "P0_MX1") (pintype "bidirectional"))
    )
    (net (code "88") (name "Net-(LEFT_BRACKET-P0)") (class "Default")
      (node (ref "D55") (pin "A") (pinfunction "A_A") (pintype "passive"))
      (node (ref "LEFT_BRACKET") (pin "MX1") (pinfunction "P0_MX1") (pintype "bidirectional"))
    )
    (net (code "89") (name "Net-(LEFT_CBRACE-P0)") (class "Default")
      (node (ref "D18") (pin "A") (pinfunction "A_A") (pintype "passive"))
      (node (ref "LEFT_CBRACE") (pin "MX1") (pinfunction "P0_MX1") (pintype "bidirectional"))
    )
    (net (code "90") (name "Net-(LEFT_PAREN-P0)") (class "Default")
      (node (ref "D13") (pin "A") (pinfunction "A_A") (pintype "passive"))
      (node (ref "LEFT_PAREN") (pin "MX1") (pinfunction "P0_MX1") (pintype "bidirectional"))
    )
    (net (code "91") (name "Net-(LESS_THAN-P0)") (class "Default")
      (node (ref "D92") (pin "A") (pinfunction "A_A") (pintype "passive"))
      (node (ref "LESS_THAN") (pin "MX1") (pinfunction "P0_MX1") (pintype "bidirectional"))
    )
    (net (code "92") (name "Net-(LL_SPACE-P0)") (class "Default")
      (node (ref "D107") (pin "A") (pinfunction "A_A") (pintype "passive"))
      (node (ref "LL_SPACE") (pin "MX1") (pinfunction "P0_MX1") (pintype "bidirectional"))
      (node (ref "L_SPACE") (pin "MX1") (pinfunction "P0_MX1") (pintype "bidirectional"))
    )
    (net (code "93") (name "Net-(LR_SPACE-P0)") (class "Default")
      (node (ref "D108") (pin "A") (pinfunction "A_A") (pintype "passive"))
      (node (ref "LR_SPACE") (pin "MX1") (pinfunction "P0_MX1") (pintype "bidirectional"))
    )
    (net (code "94") (name "Net-(L_ALT-P0)") (class "Default")
      (node (ref "D106") (pin "A") (pinfunction "A_A") (pintype "passive"))
      (node (ref "L_ALT") (pin "MX1") (pinfunction "P0_MX1") (pintype "bidirectional"))
      (node (ref "L_SPACE1") (pin "MX1") (pinfunction "P0_MX1") (pintype "bidirectional"))
    )
    (net (code "95") (name "Net-(L_CTRL-P0)") (class "Default")
      (node (ref "D104") (pin "A") (pinfunction "A_A") (pintype "passive"))
      (node (ref "L_CTRL") (pin "MX1") (pinfunction "P0_MX1") (pintype "bidirectional"))
    )
    (net (code "96") (name "Net-(L_SHIFT-P0)") (class "Default")
      (node (ref "D84") (pin "A") (pinfunction "A_A") (pintype "passive"))
      (node (ref "L_SHIFT") (pin "MX1") (pinfunction "P0_MX1") (pintype "bidirectional"))
    )
    (net (code "97") (name "Net-(L_WIN-P0)") (class "Default")
      (node (ref "D105") (pin "A") (pinfunction "A_A") (pintype "passive"))
      (node (ref "L_WIN") (pin "MX1") (pinfunction "P0_MX1") (pintype "bidirectional"))
    )
    (net (code "98") (name "Net-(M-P0)") (class "Default")
      (node (ref "D91") (pin "A") (pinfunction "A_A") (pintype "passive"))
      (node (ref "M") (pin "MX1") (pinfunction "P0_MX1") (pintype "bidirectional"))
    )
    (net (code "99") (name "Net-(MINUS-P0)") (class "Default")
      (node (ref "D35") (pin "A") (pinfunction "A_A") (pintype "passive"))
      (node (ref "MINUS") (pin "MX1") (pinfunction "P0_MX1") (pintype "bidirectional"))
    )
    (net (code "100") (name "Net-(N-P0)") (class "Default")
      (node (ref "D90") (pin "A") (pinfunction "A_A") (pintype "passive"))
      (node (ref "N") (pin "MX1") (pinfunction "P0_MX1") (pintype "bidirectional"))
    )
    (net (code "101") (name "Net-(NUMPAD_0_BOTTOM-P0)") (class "Default")
      (node (ref "D97") (pin "A") (pinfunction "A_A") (pintype "passive"))
      (node (ref "NUMPAD_0_BOTTOM") (pin "MX1") (pinfunction "P0_MX1") (pintype "bidirectional"))
    )
    (net (code "102") (name "Net-(NUMPAD_0_FULL-P0)") (class "Default")
      (node (ref "D77") (pin "A") (pinfunction "A_A") (pintype "passive"))
      (node (ref "NUMPAD_0_FULL") (pin "MX1") (pinfunction "P0_MX1") (pintype "bidirectional"))
      (node (ref "NUMPAD_0_TOP") (pin "MX1") (pinfunction "P0_MX1") (pintype "bidirectional"))
    )
    (net (code "103") (name "Net-(NUM_1-P0)") (class "Default")
      (node (ref "D118") (pin "A") (pinfunction "A_A") (pintype "passive"))
      (node (ref "NUM_1") (pin "MX1") (pinfunction "P0_MX1") (pintype "bidirectional"))
    )
    (net (code "104") (name "Net-(NUM_2-P0)") (class "Default")
      (node (ref "D119") (pin "A") (pinfunction "A_A") (pintype "passive"))
      (node (ref "NUM_2") (pin "MX1") (pinfunction "P0_MX1") (pintype "bidirectional"))
    )
    (net (code "105") (name "Net-(NUM_3-P0)") (class "Default")
      (node (ref "D120") (pin "A") (pinfunction "A_A") (pintype "passive"))
      (node (ref "NUM_3") (pin "MX1") (pinfunction "P0_MX1") (pintype "bidirectional"))
    )
    (net (code "106") (name "Net-(NUM_4-P0)") (class "Default")
      (node (ref "D98") (pin "A") (pinfunction "A_A") (pintype "passive"))
      (node (ref "NUM_4") (pin "MX1") (pinfunction "P0_MX1") (pintype "bidirectional"))
    )
    (net (code "107") (name "Net-(NUM_5-P0)") (class "Default")
      (node (ref "D99") (pin "A") (pinfunction "A_A") (pintype "passive"))
      (node (ref "NUM_5") (pin "MX1") (pinfunction "P0_MX1") (pintype "bidirectional"))
    )
    (net (code "108") (name "Net-(NUM_6-P0)") (class "Default")
      (node (ref "D100") (pin "A") (pinfunction "A_A") (pintype "passive"))
      (node (ref "NUM_6") (pin "MX1") (pinfunction "P0_MX1") (pintype "bidirectional"))
    )
    (net (code "109") (name "Net-(NUM_7-P0)") (class "Default")
      (node (ref "D78") (pin "A") (pinfunction "A_A") (pintype "passive"))
      (node (ref "NUM_7") (pin "MX1") (pinfunction "P0_MX1") (pintype "bidirectional"))
    )
    (net (code "110") (name "Net-(NUM_8-P0)") (class "Default")
      (node (ref "D79") (pin "A") (pinfunction "A_A") (pintype "passive"))
      (node (ref "NUM_8") (pin "MX1") (pinfunction "P0_MX1") (pintype "bidirectional"))
    )
    (net (code "111") (name "Net-(NUM_9-P0)") (class "Default")
      (node (ref "D80") (pin "A") (pinfunction "A_A") (pintype "passive"))
      (node (ref "NUM_9") (pin "MX1") (pinfunction "P0_MX1") (pintype "bidirectional"))
    )
    (net (code "112") (name "Net-(O-P0)") (class "Default")
      (node (ref "D53") (pin "A") (pinfunction "A_A") (pintype "passive"))
      (node (ref "O") (pin "MX1") (pinfunction "P0_MX1") (pintype "bidirectional"))
    )
    (net (code "113") (name "Net-(P-P0)") (class "Default")
      (node (ref "D54") (pin "A") (pinfunction "A_A") (pintype "passive"))
      (node (ref "P") (pin "MX1") (pinfunction "P0_MX1") (pintype "bidirectional"))
    )
    (net (code "114") (name "Net-(PASTE-P0)") (class "Default")
      (node (ref "D103") (pin "A") (pinfunction "A_A") (pintype "passive"))
      (node (ref "PASTE") (pin "MX1") (pinfunction "P0_MX1") (pintype "bidirectional"))
    )
    (net (code "115") (name "Net-(PAUSE_BREAK-P0)") (class "Default")
      (node (ref "D83") (pin "A") (pinfunction "A_A") (pintype "passive"))
      (node (ref "PAUSE_BREAK") (pin "MX1") (pinfunction "P0_MX1") (pintype "bidirectional"))
    )
    (net (code "116") (name "Net-(PERCENT-P0)") (class "Default")
      (node (ref "D9") (pin "A") (pinfunction "A_A") (pintype "passive"))
      (node (ref "PERCENT") (pin "MX1") (pinfunction "P0_MX1") (pintype "bidirectional"))
    )
    (net (code "117") (name "Net-(PERIOD-P0)") (class "Default")
      (node (ref "D113") (pin "A") (pinfunction "A_A") (pintype "passive"))
      (node (ref "PERIOD") (pin "MX1") (pinfunction "P0_MX1") (pintype "bidirectional"))
    )
    (net (code "118") (name "Net-(PG_DOWN-P0)") (class "Default")
      (node (ref "D60") (pin "A") (pinfunction "A_A") (pintype "passive"))
      (node (ref "PG_DOWN") (pin "MX1") (pinfunction "P0_MX1") (pintype "bidirectional"))
    )
    (net (code "119") (name "Net-(PG_UP-P0)") (class "Default")
      (node (ref "D40") (pin "A") (pinfunction "A_A") (pintype "passive"))
      (node (ref "PG_UP") (pin "MX1") (pinfunction "P0_MX1") (pintype "bidirectional"))
    )
    (net (code "120") (name "Net-(PIPE-P0)") (class "Default")
      (node (ref "D20") (pin "A") (pinfunction "A_A") (pintype "passive"))
      (node (ref "PIPE") (pin "MX1") (pinfunction "P0_MX1") (pintype "bidirectional"))
    )
    (net (code "121") (name "Net-(PLUS-P0)") (class "Default")
      (node (ref "D16") (pin "A") (pinfunction "A_A") (pintype "passive"))
      (node (ref "PLUS") (pin "MX1") (pinfunction "P0_MX1") (pintype "bidirectional"))
    )
    (net (code "122") (name "Net-(PRINT_SCREEN-P0)") (class "Default")
      (node (ref "D81") (pin "A") (pinfunction "A_A") (pintype "passive"))
      (node (ref "PRINT_SCREEN") (pin "MX1") (pinfunction "P0_MX1") (pintype "bidirectional"))
    )
    (net (code "123") (name "Net-(Q-P0)") (class "Default")
      (node (ref "D45") (pin "A") (pinfunction "A_A") (pintype "passive"))
      (node (ref "Q") (pin "MX1") (pinfunction "P0_MX1") (pintype "bidirectional"))
    )
    (net (code "124") (name "Net-(QUESTION_MARK-P0)") (class "Default")
      (node (ref "D94") (pin "A") (pinfunction "A_A") (pintype "passive"))
      (node (ref "QUESTION_MARK") (pin "MX1") (pinfunction "P0_MX1") (pintype "bidirectional"))
    )
    (net (code "125") (name "Net-(R-P0)") (class "Default")
      (node (ref "D48") (pin "A") (pinfunction "A_A") (pintype "passive"))
      (node (ref "R") (pin "MX1") (pinfunction "P0_MX1") (pintype "bidirectional"))
    )
    (net (code "126") (name "Net-(RIGHT-P0)") (class "Default")
      (node (ref "D117") (pin "A") (pinfunction "A_A") (pintype "passive"))
      (node (ref "RIGHT") (pin "MX1") (pinfunction "P0_MX1") (pintype "bidirectional"))
    )
    (net (code "127") (name "Net-(RIGHT_BRACKET-P0)") (class "Default")
      (node (ref "D56") (pin "A") (pinfunction "A_A") (pintype "passive"))
      (node (ref "RIGHT_BRACKET") (pin "MX1") (pinfunction "P0_MX1") (pintype "bidirectional"))
    )
    (net (code "128") (name "Net-(RIGHT_CBRACE-P0)") (class "Default")
      (node (ref "D19") (pin "A") (pinfunction "A_A") (pintype "passive"))
      (node (ref "RIGHT_CBRACE") (pin "MX1") (pinfunction "P0_MX1") (pintype "bidirectional"))
    )
    (net (code "129") (name "Net-(RIGHT_PAREN-P0)") (class "Default")
      (node (ref "D14") (pin "A") (pinfunction "A_A") (pintype "passive"))
      (node (ref "RIGHT_PAREN") (pin "MX1") (pinfunction "P0_MX1") (pintype "bidirectional"))
    )
    (net (code "130") (name "Net-(RL_SPACE-P0)") (class "Default")
      (node (ref "D110") (pin "A") (pinfunction "A_A") (pintype "passive"))
      (node (ref "RL_SPACE") (pin "MX1") (pinfunction "P0_MX1") (pintype "bidirectional"))
      (node (ref "R_SPACE") (pin "MX1") (pinfunction "P0_MX1") (pintype "bidirectional"))
    )
    (net (code "131") (name "Net-(RR_SPACE-P0)") (class "Default")
      (node (ref "D111") (pin "A") (pinfunction "A_A") (pintype "passive"))
      (node (ref "RR_SPACE") (pin "MX1") (pinfunction "P0_MX1") (pintype "bidirectional"))
    )
    (net (code "132") (name "Net-(R_SHIFT-P0)") (class "Default")
      (node (ref "D95") (pin "A") (pinfunction "A_A") (pintype "passive"))
      (node (ref "R_SHIFT") (pin "MX1") (pinfunction "P0_MX1") (pintype "bidirectional"))
    )
    (net (code "133") (name "Net-(S-P0)") (class "Default")
      (node (ref "D66") (pin "A") (pinfunction "A_A") (pintype "passive"))
      (node (ref "S") (pin "MX1") (pinfunction "P0_MX1") (pintype "bidirectional"))
    )
    (net (code "134") (name "Net-(SCROLL_LOCK-P0)") (class "Default")
      (node (ref "D82") (pin "A") (pinfunction "A_A") (pintype "passive"))
      (node (ref "SCROLL_LOCK") (pin "MX1") (pinfunction "P0_MX1") (pintype "bidirectional"))
    )
    (net (code "135") (name "Net-(SEMICOLON-P0)") (class "Default")
      (node (ref "D58") (pin "A") (pinfunction "A_A") (pintype "passive"))
      (node (ref "SEMICOLON") (pin "MX1") (pinfunction "P0_MX1") (pintype "bidirectional"))
    )
    (net (code "136") (name "Net-(SINGLE_QUOTE-P0)") (class "Default")
      (node (ref "D75") (pin "A") (pinfunction "A_A") (pintype "passive"))
      (node (ref "SINGLE_QUOTE") (pin "MX1") (pinfunction "P0_MX1") (pintype "bidirectional"))
    )
    (net (code "137") (name "Net-(T-P0)") (class "Default")
      (node (ref "D49") (pin "A") (pinfunction "A_A") (pintype "passive"))
      (node (ref "T") (pin "MX1") (pinfunction "P0_MX1") (pintype "bidirectional"))
    )
    (net (code "138") (name "Net-(TAB-P0)") (class "Default")
      (node (ref "D44") (pin "A") (pinfunction "A_A") (pintype "passive"))
      (node (ref "TAB") (pin "MX1") (pinfunction "P0_MX1") (pintype "bidirectional"))
    )
    (net (code "139") (name "Net-(TILDE-P0)") (class "Default")
      (node (ref "D4") (pin "A") (pinfunction "A_A") (pintype "passive"))
      (node (ref "TILDE") (pin "MX1") (pinfunction "P0_MX1") (pintype "bidirectional"))
    )
    (net (code "140") (name "Net-(U-P0)") (class "Default")
      (node (ref "D51") (pin "A") (pinfunction "A_A") (pintype "passive"))
      (node (ref "U") (pin "MX1") (pinfunction "P0_MX1") (pintype "bidirectional"))
    )
    (net (code "141") (name "Net-(UNDESCORE-P0)") (class "Default")
      (node (ref "D15") (pin "A") (pinfunction "A_A") (pintype "passive"))
      (node (ref "UNDESCORE") (pin "MX1") (pinfunction "P0_MX1") (pintype "bidirectional"))
    )
    (net (code "142") (name "Net-(UP-P0)") (class "Default")
      (node (ref "D96") (pin "A") (pinfunction "A_A") (pintype "passive"))
      (node (ref "UP") (pin "MX1") (pinfunction "P0_MX1") (pintype "bidirectional"))
    )
    (net (code "143") (name "Net-(V-P0)") (class "Default")
      (node (ref "D88") (pin "A") (pinfunction "A_A") (pintype "passive"))
      (node (ref "V") (pin "MX1") (pinfunction "P0_MX1") (pintype "bidirectional"))
    )
    (net (code "144") (name "Net-(W-P0)") (class "Default")
      (node (ref "D46") (pin "A") (pinfunction "A_A") (pintype "passive"))
      (node (ref "W") (pin "MX1") (pinfunction "P0_MX1") (pintype "bidirectional"))
    )
    (net (code "145") (name "Net-(X-P0)") (class "Default")
      (node (ref "D86") (pin "A") (pinfunction "A_A") (pintype "passive"))
      (node (ref "X") (pin "MX1") (pinfunction "P0_MX1") (pintype "bidirectional"))
    )
    (net (code "146") (name "Net-(Y-P0)") (class "Default")
      (node (ref "D50") (pin "A") (pinfunction "A_A") (pintype "passive"))
      (node (ref "Y") (pin "MX1") (pinfunction "P0_MX1") (pintype "bidirectional"))
    )
    (net (code "147") (name "Net-(Z-P0)") (class "Default")
      (node (ref "D85") (pin "A") (pinfunction "A_A") (pintype "passive"))
      (node (ref "Z") (pin "MX1") (pinfunction "P0_MX1") (pintype "bidirectional"))
    )
    (net (code "148") (name "unconnected-(J1-Pad1)") (class "Default")
      (node (ref "J1") (pin "1") (pinfunction "1_1") (pintype "bidirectional"))
    )
    (net (code "149") (name "unconnected-(J1-Pad2)") (class "Default")
      (node (ref "J1") (pin "2") (pinfunction "2_2") (pintype "bidirectional"))
    )
    (net (code "150") (name "unconnected-(J1-Pad3)") (class "Default")
      (node (ref "J1") (pin "3") (pinfunction "3_3") (pintype "bidirectional"))
    )
    (net (code "151") (name "unconnected-(J1-Pad4)") (class "Default")
      (node (ref "J1") (pin "4") (pinfunction "4_4") (pintype "bidirectional"))
    )
    (net (code "152") (name "unconnected-(J1-Pad5)") (class "Default")
      (node (ref "J1") (pin "5") (pinfunction "5_5") (pintype "bidirectional"))
    )
    (net (code "153") (name "unconnected-(J1-Pad6)") (class "Default")
      (node (ref "J1") (pin "6") (pinfunction "6_6") (pintype "bidirectional"))
    )
    (net (code "154") (name "unconnected-(J1-Pad7)") (class "Default")
      (node (ref "J1") (pin "7") (pinfunction "7_7") (pintype "bidirectional"))
    )
    (net (code "155") (name "unconnected-(J1-Pad8)") (class "Default")
      (node (ref "J1") (pin "8") (pinfunction "8_8") (pintype "bidirectional"))
    )
    (net (code "156") (name "unconnected-(J1-Pad9)") (class "Default")
      (node (ref "J1") (pin "9") (pinfunction "9_9") (pintype "bidirectional"))
    )
    (net (code "157") (name "unconnected-(J1-Pad11)") (class "Default")
      (node (ref "J1") (pin "11") (pinfunction "11_11") (pintype "bidirectional"))
    )
    (net (code "158") (name "unconnected-(J2-Pad4)") (class "Default")
      (node (ref "J2") (pin "4") (pinfunction "4_4") (pintype "bidirectional"))
    )
    (net (code "159") (name "unconnected-(U$1-Pad1)") (class "Default")
      (node (ref "U$1") (pin "1") (pinfunction "1_1") (pintype "bidirectional"))
    )
  )
)
